# Wordclock.net
KiCad netlist of a schematic drawn in EAGLE
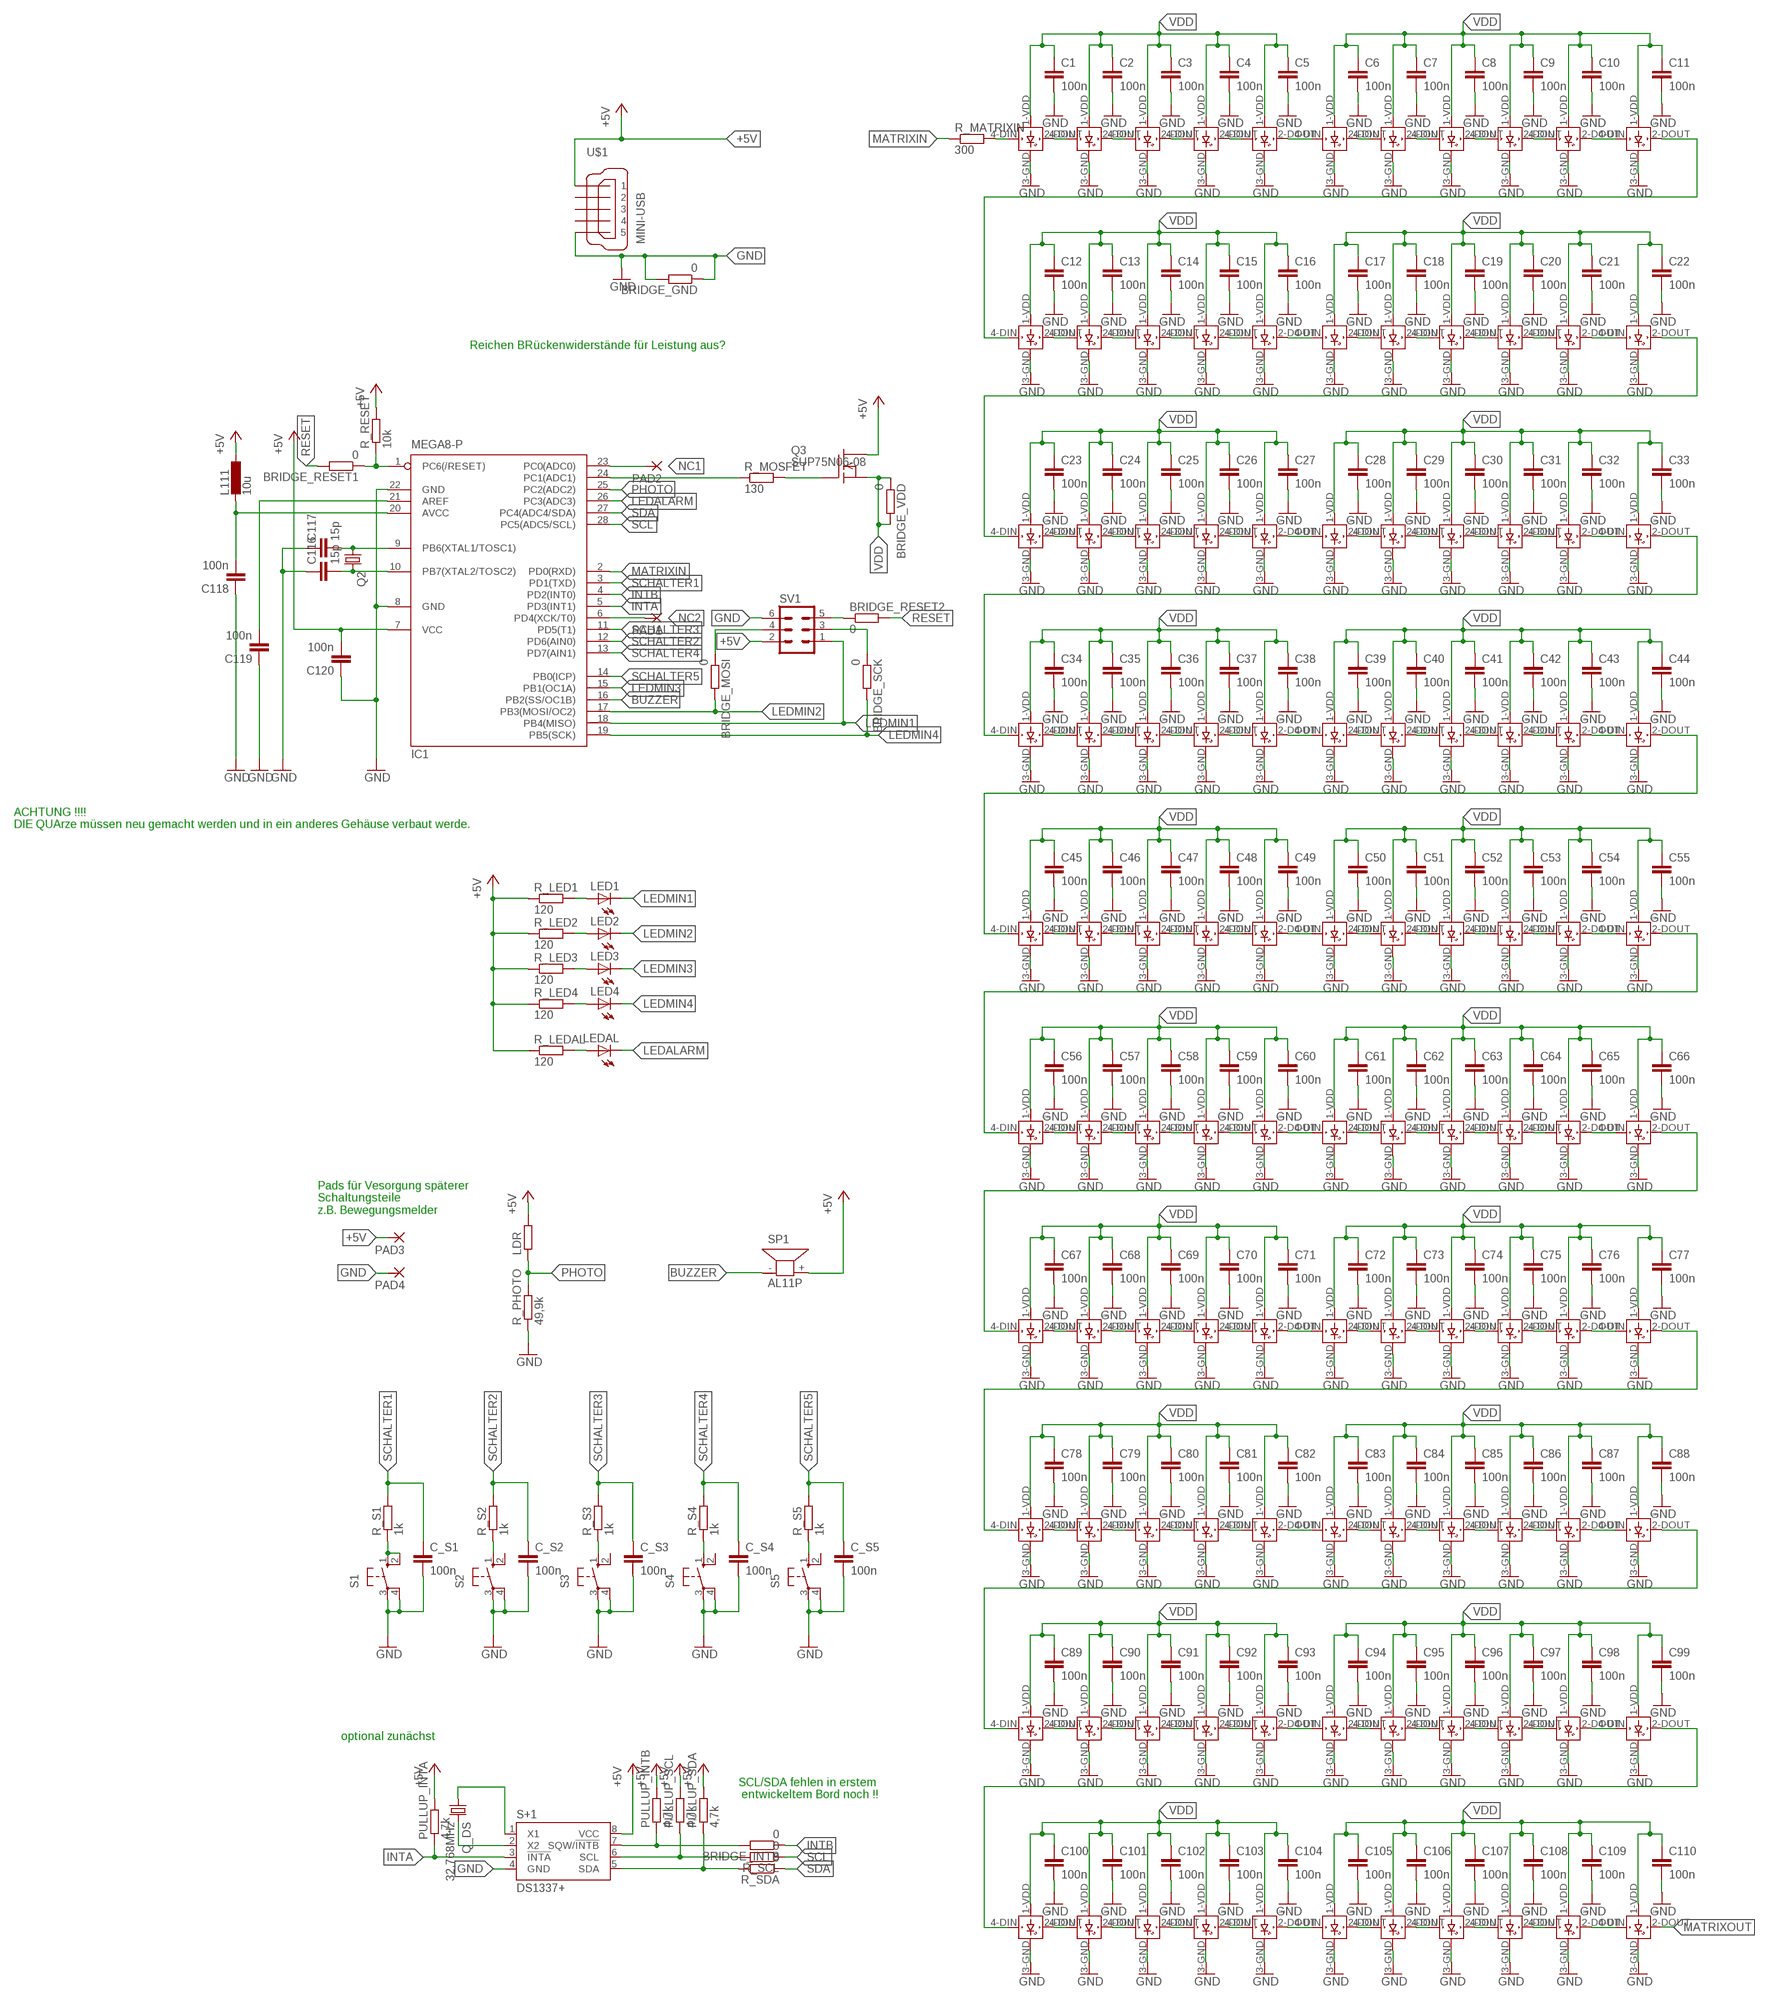
[diagram p0: schematic, sheet 1]

(export (version "E")
  (design (tool "Eeschema 10.0.6"))
  (components
    (comp (ref "BRIDGE_GND")
      (value "0")
      (footprint "eagle-import:R1206")
      (libsource (lib "eagle-import") (part "R-EU_R1206"))
    )
    (comp (ref "BRIDGE_INTB")
      (value "0")
      (footprint "eagle-import:R1206")
      (libsource (lib "eagle-import") (part "R-EU_R1206"))
    )
    (comp (ref "BRIDGE_MOSI")
      (value "0")
      (footprint "eagle-import:R1206")
      (libsource (lib "eagle-import") (part "R-EU_R1206"))
    )
    (comp (ref "BRIDGE_RESET1")
      (value "0")
      (footprint "eagle-import:M1206")
      (libsource (lib "eagle-import") (part "R-EU_M1206"))
    )
    (comp (ref "BRIDGE_RESET2")
      (value "0")
      (footprint "eagle-import:R1206")
      (libsource (lib "eagle-import") (part "R-EU_R1206"))
    )
    (comp (ref "BRIDGE_SCK")
      (value "0")
      (footprint "eagle-import:R1206")
      (libsource (lib "eagle-import") (part "R-EU_R1206"))
    )
    (comp (ref "BRIDGE_VDD")
      (value "0")
      (footprint "eagle-import:R1206")
      (libsource (lib "eagle-import") (part "R-EU_R1206"))
    )
    (comp (ref "C1")
      (value "100n")
      (footprint "eagle-import:C1310")
      (libsource (lib "eagle-import") (part "C-EUC1310"))
    )
    (comp (ref "C2")
      (value "100n")
      (footprint "eagle-import:C1310")
      (libsource (lib "eagle-import") (part "C-EUC1310"))
    )
    (comp (ref "C3")
      (value "100n")
      (footprint "eagle-import:C1310")
      (libsource (lib "eagle-import") (part "C-EUC1310"))
    )
    (comp (ref "C4")
      (value "100n")
      (footprint "eagle-import:C1310")
      (libsource (lib "eagle-import") (part "C-EUC1310"))
    )
    (comp (ref "C5")
      (value "100n")
      (footprint "eagle-import:C1310")
      (libsource (lib "eagle-import") (part "C-EUC1310"))
    )
    (comp (ref "C6")
      (value "100n")
      (footprint "eagle-import:C1310")
      (libsource (lib "eagle-import") (part "C-EUC1310"))
    )
    (comp (ref "C7")
      (value "100n")
      (footprint "eagle-import:C1310")
      (libsource (lib "eagle-import") (part "C-EUC1310"))
    )
    (comp (ref "C8")
      (value "100n")
      (footprint "eagle-import:C1310")
      (libsource (lib "eagle-import") (part "C-EUC1310"))
    )
    (comp (ref "C9")
      (value "100n")
      (footprint "eagle-import:C1310")
      (libsource (lib "eagle-import") (part "C-EUC1310"))
    )
    (comp (ref "C10")
      (value "100n")
      (footprint "eagle-import:C1310")
      (libsource (lib "eagle-import") (part "C-EUC1310"))
    )
    (comp (ref "C11")
      (value "100n")
      (footprint "eagle-import:C1310")
      (libsource (lib "eagle-import") (part "C-EUC1310"))
    )
    (comp (ref "C12")
      (value "100n")
      (footprint "eagle-import:C1310")
      (libsource (lib "eagle-import") (part "C-EUC1310"))
    )
    (comp (ref "C13")
      (value "100n")
      (footprint "eagle-import:C1310")
      (libsource (lib "eagle-import") (part "C-EUC1310"))
    )
    (comp (ref "C14")
      (value "100n")
      (footprint "eagle-import:C1310")
      (libsource (lib "eagle-import") (part "C-EUC1310"))
    )
    (comp (ref "C15")
      (value "100n")
      (footprint "eagle-import:C1310")
      (libsource (lib "eagle-import") (part "C-EUC1310"))
    )
    (comp (ref "C16")
      (value "100n")
      (footprint "eagle-import:C1310")
      (libsource (lib "eagle-import") (part "C-EUC1310"))
    )
    (comp (ref "C17")
      (value "100n")
      (footprint "eagle-import:C1310")
      (libsource (lib "eagle-import") (part "C-EUC1310"))
    )
    (comp (ref "C18")
      (value "100n")
      (footprint "eagle-import:C1310")
      (libsource (lib "eagle-import") (part "C-EUC1310"))
    )
    (comp (ref "C19")
      (value "100n")
      (footprint "eagle-import:C1310")
      (libsource (lib "eagle-import") (part "C-EUC1310"))
    )
    (comp (ref "C20")
      (value "100n")
      (footprint "eagle-import:C1310")
      (libsource (lib "eagle-import") (part "C-EUC1310"))
    )
    (comp (ref "C21")
      (value "100n")
      (footprint "eagle-import:C1310")
      (libsource (lib "eagle-import") (part "C-EUC1310"))
    )
    (comp (ref "C22")
      (value "100n")
      (footprint "eagle-import:C1310")
      (libsource (lib "eagle-import") (part "C-EUC1310"))
    )
    (comp (ref "C23")
      (value "100n")
      (footprint "eagle-import:C1310")
      (libsource (lib "eagle-import") (part "C-EUC1310"))
    )
    (comp (ref "C24")
      (value "100n")
      (footprint "eagle-import:C1310")
      (libsource (lib "eagle-import") (part "C-EUC1310"))
    )
    (comp (ref "C25")
      (value "100n")
      (footprint "eagle-import:C1310")
      (libsource (lib "eagle-import") (part "C-EUC1310"))
    )
    (comp (ref "C26")
      (value "100n")
      (footprint "eagle-import:C1310")
      (libsource (lib "eagle-import") (part "C-EUC1310"))
    )
    (comp (ref "C27")
      (value "100n")
      (footprint "eagle-import:C1310")
      (libsource (lib "eagle-import") (part "C-EUC1310"))
    )
    (comp (ref "C28")
      (value "100n")
      (footprint "eagle-import:C1310")
      (libsource (lib "eagle-import") (part "C-EUC1310"))
    )
    (comp (ref "C29")
      (value "100n")
      (footprint "eagle-import:C1310")
      (libsource (lib "eagle-import") (part "C-EUC1310"))
    )
    (comp (ref "C30")
      (value "100n")
      (footprint "eagle-import:C1310")
      (libsource (lib "eagle-import") (part "C-EUC1310"))
    )
    (comp (ref "C31")
      (value "100n")
      (footprint "eagle-import:C1310")
      (libsource (lib "eagle-import") (part "C-EUC1310"))
    )
    (comp (ref "C32")
      (value "100n")
      (footprint "eagle-import:C1310")
      (libsource (lib "eagle-import") (part "C-EUC1310"))
    )
    (comp (ref "C33")
      (value "100n")
      (footprint "eagle-import:C1310")
      (libsource (lib "eagle-import") (part "C-EUC1310"))
    )
    (comp (ref "C34")
      (value "100n")
      (footprint "eagle-import:C1310")
      (libsource (lib "eagle-import") (part "C-EUC1310"))
    )
    (comp (ref "C35")
      (value "100n")
      (footprint "eagle-import:C1310")
      (libsource (lib "eagle-import") (part "C-EUC1310"))
    )
    (comp (ref "C36")
      (value "100n")
      (footprint "eagle-import:C1310")
      (libsource (lib "eagle-import") (part "C-EUC1310"))
    )
    (comp (ref "C37")
      (value "100n")
      (footprint "eagle-import:C1310")
      (libsource (lib "eagle-import") (part "C-EUC1310"))
    )
    (comp (ref "C38")
      (value "100n")
      (footprint "eagle-import:C1310")
      (libsource (lib "eagle-import") (part "C-EUC1310"))
    )
    (comp (ref "C39")
      (value "100n")
      (footprint "eagle-import:C1310")
      (libsource (lib "eagle-import") (part "C-EUC1310"))
    )
    (comp (ref "C40")
      (value "100n")
      (footprint "eagle-import:C1310")
      (libsource (lib "eagle-import") (part "C-EUC1310"))
    )
    (comp (ref "C41")
      (value "100n")
      (footprint "eagle-import:C1310")
      (libsource (lib "eagle-import") (part "C-EUC1310"))
    )
    (comp (ref "C42")
      (value "100n")
      (footprint "eagle-import:C1310")
      (libsource (lib "eagle-import") (part "C-EUC1310"))
    )
    (comp (ref "C43")
      (value "100n")
      (footprint "eagle-import:C1310")
      (libsource (lib "eagle-import") (part "C-EUC1310"))
    )
    (comp (ref "C44")
      (value "100n")
      (footprint "eagle-import:C1310")
      (libsource (lib "eagle-import") (part "C-EUC1310"))
    )
    (comp (ref "C45")
      (value "100n")
      (footprint "eagle-import:C1310")
      (libsource (lib "eagle-import") (part "C-EUC1310"))
    )
    (comp (ref "C46")
      (value "100n")
      (footprint "eagle-import:C1310")
      (libsource (lib "eagle-import") (part "C-EUC1310"))
    )
    (comp (ref "C47")
      (value "100n")
      (footprint "eagle-import:C1310")
      (libsource (lib "eagle-import") (part "C-EUC1310"))
    )
    (comp (ref "C48")
      (value "100n")
      (footprint "eagle-import:C1310")
      (libsource (lib "eagle-import") (part "C-EUC1310"))
    )
    (comp (ref "C49")
      (value "100n")
      (footprint "eagle-import:C1310")
      (libsource (lib "eagle-import") (part "C-EUC1310"))
    )
    (comp (ref "C50")
      (value "100n")
      (footprint "eagle-import:C1310")
      (libsource (lib "eagle-import") (part "C-EUC1310"))
    )
    (comp (ref "C51")
      (value "100n")
      (footprint "eagle-import:C1310")
      (libsource (lib "eagle-import") (part "C-EUC1310"))
    )
    (comp (ref "C52")
      (value "100n")
      (footprint "eagle-import:C1310")
      (libsource (lib "eagle-import") (part "C-EUC1310"))
    )
    (comp (ref "C53")
      (value "100n")
      (footprint "eagle-import:C1310")
      (libsource (lib "eagle-import") (part "C-EUC1310"))
    )
    (comp (ref "C54")
      (value "100n")
      (footprint "eagle-import:C1310")
      (libsource (lib "eagle-import") (part "C-EUC1310"))
    )
    (comp (ref "C55")
      (value "100n")
      (footprint "eagle-import:C1310")
      (libsource (lib "eagle-import") (part "C-EUC1310"))
    )
    (comp (ref "C56")
      (value "100n")
      (footprint "eagle-import:C1310")
      (libsource (lib "eagle-import") (part "C-EUC1310"))
    )
    (comp (ref "C57")
      (value "100n")
      (footprint "eagle-import:C1310")
      (libsource (lib "eagle-import") (part "C-EUC1310"))
    )
    (comp (ref "C58")
      (value "100n")
      (footprint "eagle-import:C1310")
      (libsource (lib "eagle-import") (part "C-EUC1310"))
    )
    (comp (ref "C59")
      (value "100n")
      (footprint "eagle-import:C1310")
      (libsource (lib "eagle-import") (part "C-EUC1310"))
    )
    (comp (ref "C60")
      (value "100n")
      (footprint "eagle-import:C1310")
      (libsource (lib "eagle-import") (part "C-EUC1310"))
    )
    (comp (ref "C61")
      (value "100n")
      (footprint "eagle-import:C1310")
      (libsource (lib "eagle-import") (part "C-EUC1310"))
    )
    (comp (ref "C62")
      (value "100n")
      (footprint "eagle-import:C1310")
      (libsource (lib "eagle-import") (part "C-EUC1310"))
    )
    (comp (ref "C63")
      (value "100n")
      (footprint "eagle-import:C1310")
      (libsource (lib "eagle-import") (part "C-EUC1310"))
    )
    (comp (ref "C64")
      (value "100n")
      (footprint "eagle-import:C1310")
      (libsource (lib "eagle-import") (part "C-EUC1310"))
    )
    (comp (ref "C65")
      (value "100n")
      (footprint "eagle-import:C1310")
      (libsource (lib "eagle-import") (part "C-EUC1310"))
    )
    (comp (ref "C66")
      (value "100n")
      (footprint "eagle-import:C1310")
      (libsource (lib "eagle-import") (part "C-EUC1310"))
    )
    (comp (ref "C67")
      (value "100n")
      (footprint "eagle-import:C1310")
      (libsource (lib "eagle-import") (part "C-EUC1310"))
    )
    (comp (ref "C68")
      (value "100n")
      (footprint "eagle-import:C1310")
      (libsource (lib "eagle-import") (part "C-EUC1310"))
    )
    (comp (ref "C69")
      (value "100n")
      (footprint "eagle-import:C1310")
      (libsource (lib "eagle-import") (part "C-EUC1310"))
    )
    (comp (ref "C70")
      (value "100n")
      (footprint "eagle-import:C1310")
      (libsource (lib "eagle-import") (part "C-EUC1310"))
    )
    (comp (ref "C71")
      (value "100n")
      (footprint "eagle-import:C1310")
      (libsource (lib "eagle-import") (part "C-EUC1310"))
    )
    (comp (ref "C72")
      (value "100n")
      (footprint "eagle-import:C1310")
      (libsource (lib "eagle-import") (part "C-EUC1310"))
    )
    (comp (ref "C73")
      (value "100n")
      (footprint "eagle-import:C1310")
      (libsource (lib "eagle-import") (part "C-EUC1310"))
    )
    (comp (ref "C74")
      (value "100n")
      (footprint "eagle-import:C1310")
      (libsource (lib "eagle-import") (part "C-EUC1310"))
    )
    (comp (ref "C75")
      (value "100n")
      (footprint "eagle-import:C1310")
      (libsource (lib "eagle-import") (part "C-EUC1310"))
    )
    (comp (ref "C76")
      (value "100n")
      (footprint "eagle-import:C1310")
      (libsource (lib "eagle-import") (part "C-EUC1310"))
    )
    (comp (ref "C77")
      (value "100n")
      (footprint "eagle-import:C1310")
      (libsource (lib "eagle-import") (part "C-EUC1310"))
    )
    (comp (ref "C78")
      (value "100n")
      (footprint "eagle-import:C1310")
      (libsource (lib "eagle-import") (part "C-EUC1310"))
    )
    (comp (ref "C79")
      (value "100n")
      (footprint "eagle-import:C1310")
      (libsource (lib "eagle-import") (part "C-EUC1310"))
    )
    (comp (ref "C80")
      (value "100n")
      (footprint "eagle-import:C1310")
      (libsource (lib "eagle-import") (part "C-EUC1310"))
    )
    (comp (ref "C81")
      (value "100n")
      (footprint "eagle-import:C1310")
      (libsource (lib "eagle-import") (part "C-EUC1310"))
    )
    (comp (ref "C82")
      (value "100n")
      (footprint "eagle-import:C1310")
      (libsource (lib "eagle-import") (part "C-EUC1310"))
    )
    (comp (ref "C83")
      (value "100n")
      (footprint "eagle-import:C1310")
      (libsource (lib "eagle-import") (part "C-EUC1310"))
    )
    (comp (ref "C84")
      (value "100n")
      (footprint "eagle-import:C1310")
      (libsource (lib "eagle-import") (part "C-EUC1310"))
    )
    (comp (ref "C85")
      (value "100n")
      (footprint "eagle-import:C1310")
      (libsource (lib "eagle-import") (part "C-EUC1310"))
    )
    (comp (ref "C86")
      (value "100n")
      (footprint "eagle-import:C1310")
      (libsource (lib "eagle-import") (part "C-EUC1310"))
    )
    (comp (ref "C87")
      (value "100n")
      (footprint "eagle-import:C1310")
      (libsource (lib "eagle-import") (part "C-EUC1310"))
    )
    (comp (ref "C88")
      (value "100n")
      (footprint "eagle-import:C1310")
      (libsource (lib "eagle-import") (part "C-EUC1310"))
    )
    (comp (ref "C89")
      (value "100n")
      (footprint "eagle-import:C1310")
      (libsource (lib "eagle-import") (part "C-EUC1310"))
    )
    (comp (ref "C90")
      (value "100n")
      (footprint "eagle-import:C1310")
      (libsource (lib "eagle-import") (part "C-EUC1310"))
    )
    (comp (ref "C91")
      (value "100n")
      (footprint "eagle-import:C1310")
      (libsource (lib "eagle-import") (part "C-EUC1310"))
    )
    (comp (ref "C92")
      (value "100n")
      (footprint "eagle-import:C1310")
      (libsource (lib "eagle-import") (part "C-EUC1310"))
    )
    (comp (ref "C93")
      (value "100n")
      (footprint "eagle-import:C1310")
      (libsource (lib "eagle-import") (part "C-EUC1310"))
    )
    (comp (ref "C94")
      (value "100n")
      (footprint "eagle-import:C1310")
      (libsource (lib "eagle-import") (part "C-EUC1310"))
    )
    (comp (ref "C95")
      (value "100n")
      (footprint "eagle-import:C1310")
      (libsource (lib "eagle-import") (part "C-EUC1310"))
    )
    (comp (ref "C96")
      (value "100n")
      (footprint "eagle-import:C1310")
      (libsource (lib "eagle-import") (part "C-EUC1310"))
    )
    (comp (ref "C97")
      (value "100n")
      (footprint "eagle-import:C1310")
      (libsource (lib "eagle-import") (part "C-EUC1310"))
    )
    (comp (ref "C98")
      (value "100n")
      (footprint "eagle-import:C1310")
      (libsource (lib "eagle-import") (part "C-EUC1310"))
    )
    (comp (ref "C99")
      (value "100n")
      (footprint "eagle-import:C1310")
      (libsource (lib "eagle-import") (part "C-EUC1310"))
    )
    (comp (ref "C100")
      (value "100n")
      (footprint "eagle-import:C1310")
      (libsource (lib "eagle-import") (part "C-EUC1310"))
    )
    (comp (ref "C101")
      (value "100n")
      (footprint "eagle-import:C1310")
      (libsource (lib "eagle-import") (part "C-EUC1310"))
    )
    (comp (ref "C102")
      (value "100n")
      (footprint "eagle-import:C1310")
      (libsource (lib "eagle-import") (part "C-EUC1310"))
    )
    (comp (ref "C103")
      (value "100n")
      (footprint "eagle-import:C1310")
      (libsource (lib "eagle-import") (part "C-EUC1310"))
    )
    (comp (ref "C104")
      (value "100n")
      (footprint "eagle-import:C1310")
      (libsource (lib "eagle-import") (part "C-EUC1310"))
    )
    (comp (ref "C105")
      (value "100n")
      (footprint "eagle-import:C1310")
      (libsource (lib "eagle-import") (part "C-EUC1310"))
    )
    (comp (ref "C106")
      (value "100n")
      (footprint "eagle-import:C1310")
      (libsource (lib "eagle-import") (part "C-EUC1310"))
    )
    (comp (ref "C107")
      (value "100n")
      (footprint "eagle-import:C1310")
      (libsource (lib "eagle-import") (part "C-EUC1310"))
    )
    (comp (ref "C108")
      (value "100n")
      (footprint "eagle-import:C1310")
      (libsource (lib "eagle-import") (part "C-EUC1310"))
    )
    (comp (ref "C109")
      (value "100n")
      (footprint "eagle-import:C1310")
      (libsource (lib "eagle-import") (part "C-EUC1310"))
    )
    (comp (ref "C110")
      (value "100n")
      (footprint "eagle-import:C1310")
      (libsource (lib "eagle-import") (part "C-EUC1310"))
    )
    (comp (ref "C116")
      (value "15p")
      (footprint "eagle-import:C0805")
      (libsource (lib "eagle-import") (part "C-EUC0805"))
    )
    (comp (ref "C117")
      (value "15p")
      (footprint "eagle-import:C0805")
      (libsource (lib "eagle-import") (part "C-EUC0805"))
    )
    (comp (ref "C118")
      (value "100n")
      (footprint "eagle-import:C1206")
      (libsource (lib "eagle-import") (part "C-EUC1206"))
    )
    (comp (ref "C119")
      (value "100n")
      (footprint "eagle-import:C0805")
      (libsource (lib "eagle-import") (part "C-EUC0805"))
    )
    (comp (ref "C120")
      (value "100n")
      (footprint "eagle-import:C0805")
      (libsource (lib "eagle-import") (part "C-EUC0805"))
    )
    (comp (ref "C_S1")
      (value "100n")
      (footprint "eagle-import:C1206")
      (libsource (lib "eagle-import") (part "C-EUC1206"))
    )
    (comp (ref "C_S2")
      (value "100n")
      (footprint "eagle-import:C1206")
      (libsource (lib "eagle-import") (part "C-EUC1206"))
    )
    (comp (ref "C_S3")
      (value "100n")
      (footprint "eagle-import:C1206")
      (libsource (lib "eagle-import") (part "C-EUC1206"))
    )
    (comp (ref "C_S4")
      (value "100n")
      (footprint "eagle-import:C1206")
      (libsource (lib "eagle-import") (part "C-EUC1206"))
    )
    (comp (ref "C_S5")
      (value "100n")
      (footprint "eagle-import:C1206")
      (libsource (lib "eagle-import") (part "C-EUC1206"))
    )
    (comp (ref "IC1")
      (value "MEGA8-P")
      (footprint "eagle-import:DIL28-3")
      (libsource (lib "eagle-import") (part "MEGA8-P"))
    )
    (comp (ref "L1")
      (value "WS2812B")
      (footprint "eagle-import:WS2812B")
      (libsource (lib "eagle-import") (part "WS2812B"))
    )
    (comp (ref "L2")
      (value "WS2812B")
      (footprint "eagle-import:WS2812B")
      (libsource (lib "eagle-import") (part "WS2812B"))
    )
    (comp (ref "L3")
      (value "WS2812B")
      (footprint "eagle-import:WS2812B")
      (libsource (lib "eagle-import") (part "WS2812B"))
    )
    (comp (ref "L4")
      (value "WS2812B")
      (footprint "eagle-import:WS2812B")
      (libsource (lib "eagle-import") (part "WS2812B"))
    )
    (comp (ref "L5")
      (value "WS2812B")
      (footprint "eagle-import:WS2812B")
      (libsource (lib "eagle-import") (part "WS2812B"))
    )
    (comp (ref "L6")
      (value "WS2812B")
      (footprint "eagle-import:WS2812B")
      (libsource (lib "eagle-import") (part "WS2812B"))
    )
    (comp (ref "L7")
      (value "WS2812B")
      (footprint "eagle-import:WS2812B")
      (libsource (lib "eagle-import") (part "WS2812B"))
    )
    (comp (ref "L8")
      (value "WS2812B")
      (footprint "eagle-import:WS2812B")
      (libsource (lib "eagle-import") (part "WS2812B"))
    )
    (comp (ref "L9")
      (value "WS2812B")
      (footprint "eagle-import:WS2812B")
      (libsource (lib "eagle-import") (part "WS2812B"))
    )
    (comp (ref "L10")
      (value "WS2812B")
      (footprint "eagle-import:WS2812B")
      (libsource (lib "eagle-import") (part "WS2812B"))
    )
    (comp (ref "L11")
      (value "WS2812B")
      (footprint "eagle-import:WS2812B")
      (libsource (lib "eagle-import") (part "WS2812B"))
    )
    (comp (ref "L12")
      (value "WS2812B")
      (footprint "eagle-import:WS2812B")
      (libsource (lib "eagle-import") (part "WS2812B"))
    )
    (comp (ref "L13")
      (value "WS2812B")
      (footprint "eagle-import:WS2812B")
      (libsource (lib "eagle-import") (part "WS2812B"))
    )
    (comp (ref "L14")
      (value "WS2812B")
      (footprint "eagle-import:WS2812B")
      (libsource (lib "eagle-import") (part "WS2812B"))
    )
    (comp (ref "L15")
      (value "WS2812B")
      (footprint "eagle-import:WS2812B")
      (libsource (lib "eagle-import") (part "WS2812B"))
    )
    (comp (ref "L16")
      (value "WS2812B")
      (footprint "eagle-import:WS2812B")
      (libsource (lib "eagle-import") (part "WS2812B"))
    )
    (comp (ref "L17")
      (value "WS2812B")
      (footprint "eagle-import:WS2812B")
      (libsource (lib "eagle-import") (part "WS2812B"))
    )
    (comp (ref "L18")
      (value "WS2812B")
      (footprint "eagle-import:WS2812B")
      (libsource (lib "eagle-import") (part "WS2812B"))
    )
    (comp (ref "L19")
      (value "WS2812B")
      (footprint "eagle-import:WS2812B")
      (libsource (lib "eagle-import") (part "WS2812B"))
    )
    (comp (ref "L20")
      (value "WS2812B")
      (footprint "eagle-import:WS2812B")
      (libsource (lib "eagle-import") (part "WS2812B"))
    )
    (comp (ref "L21")
      (value "WS2812B")
      (footprint "eagle-import:WS2812B")
      (libsource (lib "eagle-import") (part "WS2812B"))
    )
    (comp (ref "L22")
      (value "WS2812B")
      (footprint "eagle-import:WS2812B")
      (libsource (lib "eagle-import") (part "WS2812B"))
    )
    (comp (ref "L23")
      (value "WS2812B")
      (footprint "eagle-import:WS2812B")
      (libsource (lib "eagle-import") (part "WS2812B"))
    )
    (comp (ref "L24")
      (value "WS2812B")
      (footprint "eagle-import:WS2812B")
      (libsource (lib "eagle-import") (part "WS2812B"))
    )
    (comp (ref "L25")
      (value "WS2812B")
      (footprint "eagle-import:WS2812B")
      (libsource (lib "eagle-import") (part "WS2812B"))
    )
    (comp (ref "L26")
      (value "WS2812B")
      (footprint "eagle-import:WS2812B")
      (libsource (lib "eagle-import") (part "WS2812B"))
    )
    (comp (ref "L27")
      (value "WS2812B")
      (footprint "eagle-import:WS2812B")
      (libsource (lib "eagle-import") (part "WS2812B"))
    )
    (comp (ref "L28")
      (value "WS2812B")
      (footprint "eagle-import:WS2812B")
      (libsource (lib "eagle-import") (part "WS2812B"))
    )
    (comp (ref "L29")
      (value "WS2812B")
      (footprint "eagle-import:WS2812B")
      (libsource (lib "eagle-import") (part "WS2812B"))
    )
    (comp (ref "L30")
      (value "WS2812B")
      (footprint "eagle-import:WS2812B")
      (libsource (lib "eagle-import") (part "WS2812B"))
    )
    (comp (ref "L31")
      (value "WS2812B")
      (footprint "eagle-import:WS2812B")
      (libsource (lib "eagle-import") (part "WS2812B"))
    )
    (comp (ref "L32")
      (value "WS2812B")
      (footprint "eagle-import:WS2812B")
      (libsource (lib "eagle-import") (part "WS2812B"))
    )
    (comp (ref "L33")
      (value "WS2812B")
      (footprint "eagle-import:WS2812B")
      (libsource (lib "eagle-import") (part "WS2812B"))
    )
    (comp (ref "L34")
      (value "WS2812B")
      (footprint "eagle-import:WS2812B")
      (libsource (lib "eagle-import") (part "WS2812B"))
    )
    (comp (ref "L35")
      (value "WS2812B")
      (footprint "eagle-import:WS2812B")
      (libsource (lib "eagle-import") (part "WS2812B"))
    )
    (comp (ref "L36")
      (value "WS2812B")
      (footprint "eagle-import:WS2812B")
      (libsource (lib "eagle-import") (part "WS2812B"))
    )
    (comp (ref "L37")
      (value "WS2812B")
      (footprint "eagle-import:WS2812B")
      (libsource (lib "eagle-import") (part "WS2812B"))
    )
    (comp (ref "L38")
      (value "WS2812B")
      (footprint "eagle-import:WS2812B")
      (libsource (lib "eagle-import") (part "WS2812B"))
    )
    (comp (ref "L39")
      (value "WS2812B")
      (footprint "eagle-import:WS2812B")
      (libsource (lib "eagle-import") (part "WS2812B"))
    )
    (comp (ref "L40")
      (value "WS2812B")
      (footprint "eagle-import:WS2812B")
      (libsource (lib "eagle-import") (part "WS2812B"))
    )
    (comp (ref "L41")
      (value "WS2812B")
      (footprint "eagle-import:WS2812B")
      (libsource (lib "eagle-import") (part "WS2812B"))
    )
    (comp (ref "L42")
      (value "WS2812B")
      (footprint "eagle-import:WS2812B")
      (libsource (lib "eagle-import") (part "WS2812B"))
    )
    (comp (ref "L43")
      (value "WS2812B")
      (footprint "eagle-import:WS2812B")
      (libsource (lib "eagle-import") (part "WS2812B"))
    )
    (comp (ref "L44")
      (value "WS2812B")
      (footprint "eagle-import:WS2812B")
      (libsource (lib "eagle-import") (part "WS2812B"))
    )
    (comp (ref "L45")
      (value "WS2812B")
      (footprint "eagle-import:WS2812B")
      (libsource (lib "eagle-import") (part "WS2812B"))
    )
    (comp (ref "L46")
      (value "WS2812B")
      (footprint "eagle-import:WS2812B")
      (libsource (lib "eagle-import") (part "WS2812B"))
    )
    (comp (ref "L47")
      (value "WS2812B")
      (footprint "eagle-import:WS2812B")
      (libsource (lib "eagle-import") (part "WS2812B"))
    )
    (comp (ref "L48")
      (value "WS2812B")
      (footprint "eagle-import:WS2812B")
      (libsource (lib "eagle-import") (part "WS2812B"))
    )
    (comp (ref "L49")
      (value "WS2812B")
      (footprint "eagle-import:WS2812B")
      (libsource (lib "eagle-import") (part "WS2812B"))
    )
    (comp (ref "L50")
      (value "WS2812B")
      (footprint "eagle-import:WS2812B")
      (libsource (lib "eagle-import") (part "WS2812B"))
    )
    (comp (ref "L51")
      (value "WS2812B")
      (footprint "eagle-import:WS2812B")
      (libsource (lib "eagle-import") (part "WS2812B"))
    )
    (comp (ref "L52")
      (value "WS2812B")
      (footprint "eagle-import:WS2812B")
      (libsource (lib "eagle-import") (part "WS2812B"))
    )
    (comp (ref "L53")
      (value "WS2812B")
      (footprint "eagle-import:WS2812B")
      (libsource (lib "eagle-import") (part "WS2812B"))
    )
    (comp (ref "L54")
      (value "WS2812B")
      (footprint "eagle-import:WS2812B")
      (libsource (lib "eagle-import") (part "WS2812B"))
    )
    (comp (ref "L55")
      (value "WS2812B")
      (footprint "eagle-import:WS2812B")
      (libsource (lib "eagle-import") (part "WS2812B"))
    )
    (comp (ref "L56")
      (value "WS2812B")
      (footprint "eagle-import:WS2812B")
      (libsource (lib "eagle-import") (part "WS2812B"))
    )
    (comp (ref "L57")
      (value "WS2812B")
      (footprint "eagle-import:WS2812B")
      (libsource (lib "eagle-import") (part "WS2812B"))
    )
    (comp (ref "L58")
      (value "WS2812B")
      (footprint "eagle-import:WS2812B")
      (libsource (lib "eagle-import") (part "WS2812B"))
    )
    (comp (ref "L59")
      (value "WS2812B")
      (footprint "eagle-import:WS2812B")
      (libsource (lib "eagle-import") (part "WS2812B"))
    )
    (comp (ref "L60")
      (value "WS2812B")
      (footprint "eagle-import:WS2812B")
      (libsource (lib "eagle-import") (part "WS2812B"))
    )
    (comp (ref "L61")
      (value "WS2812B")
      (footprint "eagle-import:WS2812B")
      (libsource (lib "eagle-import") (part "WS2812B"))
    )
    (comp (ref "L62")
      (value "WS2812B")
      (footprint "eagle-import:WS2812B")
      (libsource (lib "eagle-import") (part "WS2812B"))
    )
    (comp (ref "L63")
      (value "WS2812B")
      (footprint "eagle-import:WS2812B")
      (libsource (lib "eagle-import") (part "WS2812B"))
    )
    (comp (ref "L64")
      (value "WS2812B")
      (footprint "eagle-import:WS2812B")
      (libsource (lib "eagle-import") (part "WS2812B"))
    )
    (comp (ref "L65")
      (value "WS2812B")
      (footprint "eagle-import:WS2812B")
      (libsource (lib "eagle-import") (part "WS2812B"))
    )
    (comp (ref "L66")
      (value "WS2812B")
      (footprint "eagle-import:WS2812B")
      (libsource (lib "eagle-import") (part "WS2812B"))
    )
    (comp (ref "L67")
      (value "WS2812B")
      (footprint "eagle-import:WS2812B")
      (libsource (lib "eagle-import") (part "WS2812B"))
    )
    (comp (ref "L68")
      (value "WS2812B")
      (footprint "eagle-import:WS2812B")
      (libsource (lib "eagle-import") (part "WS2812B"))
    )
    (comp (ref "L69")
      (value "WS2812B")
      (footprint "eagle-import:WS2812B")
      (libsource (lib "eagle-import") (part "WS2812B"))
    )
    (comp (ref "L70")
      (value "WS2812B")
      (footprint "eagle-import:WS2812B")
      (libsource (lib "eagle-import") (part "WS2812B"))
    )
    (comp (ref "L71")
      (value "WS2812B")
      (footprint "eagle-import:WS2812B")
      (libsource (lib "eagle-import") (part "WS2812B"))
    )
    (comp (ref "L72")
      (value "WS2812B")
      (footprint "eagle-import:WS2812B")
      (libsource (lib "eagle-import") (part "WS2812B"))
    )
    (comp (ref "L73")
      (value "WS2812B")
      (footprint "eagle-import:WS2812B")
      (libsource (lib "eagle-import") (part "WS2812B"))
    )
    (comp (ref "L74")
      (value "WS2812B")
      (footprint "eagle-import:WS2812B")
      (libsource (lib "eagle-import") (part "WS2812B"))
    )
    (comp (ref "L75")
      (value "WS2812B")
      (footprint "eagle-import:WS2812B")
      (libsource (lib "eagle-import") (part "WS2812B"))
    )
    (comp (ref "L76")
      (value "WS2812B")
      (footprint "eagle-import:WS2812B")
      (libsource (lib "eagle-import") (part "WS2812B"))
    )
    (comp (ref "L77")
      (value "WS2812B")
      (footprint "eagle-import:WS2812B")
      (libsource (lib "eagle-import") (part "WS2812B"))
    )
    (comp (ref "L78")
      (value "WS2812B")
      (footprint "eagle-import:WS2812B")
      (libsource (lib "eagle-import") (part "WS2812B"))
    )
    (comp (ref "L79")
      (value "WS2812B")
      (footprint "eagle-import:WS2812B")
      (libsource (lib "eagle-import") (part "WS2812B"))
    )
    (comp (ref "L80")
      (value "WS2812B")
      (footprint "eagle-import:WS2812B")
      (libsource (lib "eagle-import") (part "WS2812B"))
    )
    (comp (ref "L81")
      (value "WS2812B")
      (footprint "eagle-import:WS2812B")
      (libsource (lib "eagle-import") (part "WS2812B"))
    )
    (comp (ref "L82")
      (value "WS2812B")
      (footprint "eagle-import:WS2812B")
      (libsource (lib "eagle-import") (part "WS2812B"))
    )
    (comp (ref "L83")
      (value "WS2812B")
      (footprint "eagle-import:WS2812B")
      (libsource (lib "eagle-import") (part "WS2812B"))
    )
    (comp (ref "L84")
      (value "WS2812B")
      (footprint "eagle-import:WS2812B")
      (libsource (lib "eagle-import") (part "WS2812B"))
    )
    (comp (ref "L85")
      (value "WS2812B")
      (footprint "eagle-import:WS2812B")
      (libsource (lib "eagle-import") (part "WS2812B"))
    )
    (comp (ref "L86")
      (value "WS2812B")
      (footprint "eagle-import:WS2812B")
      (libsource (lib "eagle-import") (part "WS2812B"))
    )
    (comp (ref "L87")
      (value "WS2812B")
      (footprint "eagle-import:WS2812B")
      (libsource (lib "eagle-import") (part "WS2812B"))
    )
    (comp (ref "L88")
      (value "WS2812B")
      (footprint "eagle-import:WS2812B")
      (libsource (lib "eagle-import") (part "WS2812B"))
    )
    (comp (ref "L89")
      (value "WS2812B")
      (footprint "eagle-import:WS2812B")
      (libsource (lib "eagle-import") (part "WS2812B"))
    )
    (comp (ref "L90")
      (value "WS2812B")
      (footprint "eagle-import:WS2812B")
      (libsource (lib "eagle-import") (part "WS2812B"))
    )
    (comp (ref "L91")
      (value "WS2812B")
      (footprint "eagle-import:WS2812B")
      (libsource (lib "eagle-import") (part "WS2812B"))
    )
    (comp (ref "L92")
      (value "WS2812B")
      (footprint "eagle-import:WS2812B")
      (libsource (lib "eagle-import") (part "WS2812B"))
    )
    (comp (ref "L93")
      (value "WS2812B")
      (footprint "eagle-import:WS2812B")
      (libsource (lib "eagle-import") (part "WS2812B"))
    )
    (comp (ref "L94")
      (value "WS2812B")
      (footprint "eagle-import:WS2812B")
      (libsource (lib "eagle-import") (part "WS2812B"))
    )
    (comp (ref "L95")
      (value "WS2812B")
      (footprint "eagle-import:WS2812B")
      (libsource (lib "eagle-import") (part "WS2812B"))
    )
    (comp (ref "L96")
      (value "WS2812B")
      (footprint "eagle-import:WS2812B")
      (libsource (lib "eagle-import") (part "WS2812B"))
    )
    (comp (ref "L97")
      (value "WS2812B")
      (footprint "eagle-import:WS2812B")
      (libsource (lib "eagle-import") (part "WS2812B"))
    )
    (comp (ref "L98")
      (value "WS2812B")
      (footprint "eagle-import:WS2812B")
      (libsource (lib "eagle-import") (part "WS2812B"))
    )
    (comp (ref "L99")
      (value "WS2812B")
      (footprint "eagle-import:WS2812B")
      (libsource (lib "eagle-import") (part "WS2812B"))
    )
    (comp (ref "L100")
      (value "WS2812B")
      (footprint "eagle-import:WS2812B")
      (libsource (lib "eagle-import") (part "WS2812B"))
    )
    (comp (ref "L101")
      (value "WS2812B")
      (footprint "eagle-import:WS2812B")
      (libsource (lib "eagle-import") (part "WS2812B"))
    )
    (comp (ref "L102")
      (value "WS2812B")
      (footprint "eagle-import:WS2812B")
      (libsource (lib "eagle-import") (part "WS2812B"))
    )
    (comp (ref "L103")
      (value "WS2812B")
      (footprint "eagle-import:WS2812B")
      (libsource (lib "eagle-import") (part "WS2812B"))
    )
    (comp (ref "L104")
      (value "WS2812B")
      (footprint "eagle-import:WS2812B")
      (libsource (lib "eagle-import") (part "WS2812B"))
    )
    (comp (ref "L105")
      (value "WS2812B")
      (footprint "eagle-import:WS2812B")
      (libsource (lib "eagle-import") (part "WS2812B"))
    )
    (comp (ref "L106")
      (value "WS2812B")
      (footprint "eagle-import:WS2812B")
      (libsource (lib "eagle-import") (part "WS2812B"))
    )
    (comp (ref "L107")
      (value "WS2812B")
      (footprint "eagle-import:WS2812B")
      (libsource (lib "eagle-import") (part "WS2812B"))
    )
    (comp (ref "L108")
      (value "WS2812B")
      (footprint "eagle-import:WS2812B")
      (libsource (lib "eagle-import") (part "WS2812B"))
    )
    (comp (ref "L109")
      (value "WS2812B")
      (footprint "eagle-import:WS2812B")
      (libsource (lib "eagle-import") (part "WS2812B"))
    )
    (comp (ref "L110")
      (value "WS2812B")
      (footprint "eagle-import:WS2812B")
      (libsource (lib "eagle-import") (part "WS2812B"))
    )
    (comp (ref "L111")
      (value "10u")
      (footprint "eagle-import:L2012C")
      (libsource (lib "eagle-import") (part "L-EUL2012C"))
    )
    (comp (ref "LDR")
      (value "R-EU_0204/5")
      (footprint "eagle-import:0204_5")
      (libsource (lib "eagle-import") (part "R-EU_0204/5"))
    )
    (comp (ref "LED1")
      (value "LEDCHIPLED_1206")
      (footprint "eagle-import:CHIPLED_1206")
      (libsource (lib "eagle-import") (part "LEDCHIPLED_1206"))
    )
    (comp (ref "LED2")
      (value "LEDCHIPLED_1206")
      (footprint "eagle-import:CHIPLED_1206")
      (libsource (lib "eagle-import") (part "LEDCHIPLED_1206"))
    )
    (comp (ref "LED3")
      (value "LEDCHIPLED_1206")
      (footprint "eagle-import:CHIPLED_1206")
      (libsource (lib "eagle-import") (part "LEDCHIPLED_1206"))
    )
    (comp (ref "LED4")
      (value "LEDCHIPLED_1206")
      (footprint "eagle-import:CHIPLED_1206")
      (libsource (lib "eagle-import") (part "LEDCHIPLED_1206"))
    )
    (comp (ref "LEDAL")
      (value "LEDCHIPLED_1206")
      (footprint "eagle-import:CHIPLED_1206")
      (libsource (lib "eagle-import") (part "LEDCHIPLED_1206"))
    )
    (comp (ref "PAD1")
      (value "2,54/1,1")
      (footprint "eagle-import:2,54_1,1")
      (libsource (lib "eagle-import") (part "2,54/1,1"))
    )
    (comp (ref "PAD2")
      (value "2,54/1,1")
      (footprint "eagle-import:2,54_1,1")
      (libsource (lib "eagle-import") (part "2,54/1,1"))
    )
    (comp (ref "PAD3")
      (value "2,54/1,1")
      (footprint "eagle-import:2,54_1,1")
      (libsource (lib "eagle-import") (part "2,54/1,1"))
    )
    (comp (ref "PAD4")
      (value "2,54/1,1")
      (footprint "eagle-import:2,54_1,1")
      (libsource (lib "eagle-import") (part "2,54/1,1"))
    )
    (comp (ref "PULLUP_INTA")
      (value "4,7k")
      (footprint "eagle-import:R1206")
      (libsource (lib "eagle-import") (part "R-EU_R1206"))
    )
    (comp (ref "PULLUP_INTB")
      (value "4,7k")
      (footprint "eagle-import:R1206")
      (libsource (lib "eagle-import") (part "R-EU_R1206"))
    )
    (comp (ref "PULLUP_SCL")
      (value "4,7k")
      (footprint "eagle-import:R1206")
      (libsource (lib "eagle-import") (part "R-EU_R1206"))
    )
    (comp (ref "PULLUP_SDA")
      (value "4,7k")
      (footprint "eagle-import:R1206")
      (libsource (lib "eagle-import") (part "R-EU_R1206"))
    )
    (comp (ref "Q2")
      (value "CRYSTALHC49S")
      (footprint "eagle-import:HC49_S")
      (libsource (lib "eagle-import") (part "CRYSTALHC49S"))
    )
    (comp (ref "Q3")
      (value "SUP75N06-08")
      (footprint "eagle-import:TO220")
      (libsource (lib "eagle-import") (part "SUP75N06-08"))
    )
    (comp (ref "Q_DS")
      (value "32,768MHz")
      (footprint "eagle-import:HC49_S")
      (libsource (lib "eagle-import") (part "CRYSTALHC49S"))
    )
    (comp (ref "R_LED1")
      (value "120")
      (footprint "eagle-import:M1206")
      (libsource (lib "eagle-import") (part "R-EU_M1206"))
    )
    (comp (ref "R_LED2")
      (value "120")
      (footprint "eagle-import:M1206")
      (libsource (lib "eagle-import") (part "R-EU_M1206"))
    )
    (comp (ref "R_LED3")
      (value "120")
      (footprint "eagle-import:M1206")
      (libsource (lib "eagle-import") (part "R-EU_M1206"))
    )
    (comp (ref "R_LED4")
      (value "120")
      (footprint "eagle-import:M1206")
      (libsource (lib "eagle-import") (part "R-EU_M1206"))
    )
    (comp (ref "R_LEDAL")
      (value "120")
      (footprint "eagle-import:M1206")
      (libsource (lib "eagle-import") (part "R-EU_M1206"))
    )
    (comp (ref "R_MATRIXIN")
      (value "300")
      (footprint "eagle-import:R1206")
      (libsource (lib "eagle-import") (part "R-EU_R1206"))
    )
    (comp (ref "R_MOSFET")
      (value "130")
      (footprint "eagle-import:R1206")
      (libsource (lib "eagle-import") (part "R-EU_R1206"))
    )
    (comp (ref "R_PHOTO")
      (value "49,9k")
      (footprint "eagle-import:M1206")
      (libsource (lib "eagle-import") (part "R-EU_M1206"))
    )
    (comp (ref "R_RESET")
      (value "10k")
      (footprint "eagle-import:M1206")
      (libsource (lib "eagle-import") (part "R-EU_M1206"))
    )
    (comp (ref "R_S1")
      (value "1k")
      (footprint "eagle-import:M1206")
      (libsource (lib "eagle-import") (part "R-EU_M1206"))
    )
    (comp (ref "R_S2")
      (value "1k")
      (footprint "eagle-import:M1206")
      (libsource (lib "eagle-import") (part "R-EU_M1206"))
    )
    (comp (ref "R_S3")
      (value "1k")
      (footprint "eagle-import:M1206")
      (libsource (lib "eagle-import") (part "R-EU_M1206"))
    )
    (comp (ref "R_S4")
      (value "1k")
      (footprint "eagle-import:M1206")
      (libsource (lib "eagle-import") (part "R-EU_M1206"))
    )
    (comp (ref "R_S5")
      (value "1k")
      (footprint "eagle-import:M1206")
      (libsource (lib "eagle-import") (part "R-EU_M1206"))
    )
    (comp (ref "R_SCL")
      (value "0")
      (footprint "eagle-import:R1206")
      (libsource (lib "eagle-import") (part "R-EU_R1206"))
    )
    (comp (ref "R_SDA")
      (value "0")
      (footprint "eagle-import:R1206")
      (libsource (lib "eagle-import") (part "R-EU_R1206"))
    )
    (comp (ref "S+1")
      (value "DS1337+")
      (footprint "eagle-import:DIL8")
      (libsource (lib "eagle-import") (part "DS1337+"))
    )
    (comp (ref "S1")
      (value "10-XX")
      (footprint "eagle-import:B3F-10XX")
      (fields (field (name "MPN") "B3F-1000"))
      (libsource (lib "eagle-import") (part "10-XX"))
    )
    (comp (ref "S2")
      (value "10-XX")
      (footprint "eagle-import:B3F-10XX")
      (fields (field (name "MPN") "B3F-1000"))
      (libsource (lib "eagle-import") (part "10-XX"))
    )
    (comp (ref "S3")
      (value "10-XX")
      (footprint "eagle-import:B3F-10XX")
      (fields (field (name "MPN") "B3F-1000"))
      (libsource (lib "eagle-import") (part "10-XX"))
    )
    (comp (ref "S4")
      (value "10-XX")
      (footprint "eagle-import:B3F-10XX")
      (fields (field (name "MPN") "B3F-1000"))
      (libsource (lib "eagle-import") (part "10-XX"))
    )
    (comp (ref "S5")
      (value "10-XX")
      (footprint "eagle-import:B3F-10XX")
      (fields (field (name "MPN") "B3F-1000"))
      (libsource (lib "eagle-import") (part "10-XX"))
    )
    (comp (ref "SP1")
      (value "AL11P")
      (footprint "eagle-import:AL11P")
      (libsource (lib "eagle-import") (part "AL11P"))
    )
    (comp (ref "SV1")
      (value "ML6L")
      (footprint "eagle-import:ML6L")
      (libsource (lib "eagle-import") (part "ML6L"))
    )
    (comp (ref "U$1")
      (value "MINI-USB")
      (footprint "eagle-import:MINI-USB")
      (libsource (lib "eagle-import") (part "MINI-USB"))
    )
  )
  (nets
    (net (code "1") (name "+5V") (class "Default")
      (node (ref "C120") (pin "2") (pinfunction "2_2") (pintype "passive"))
      (node (ref "IC1") (pin "7") (pinfunction "VCC_7") (pintype "power_in"))
      (node (ref "L111") (pin "1") (pinfunction "1_1") (pintype "passive"))
      (node (ref "LDR") (pin "2") (pinfunction "2_2") (pintype "passive"))
      (node (ref "PAD3") (pin "1") (pinfunction "P_1") (pintype "passive"))
      (node (ref "PULLUP_INTA") (pin "2") (pinfunction "2_2") (pintype "passive"))
      (node (ref "PULLUP_INTB") (pin "2") (pinfunction "2_2") (pintype "passive"))
      (node (ref "PULLUP_SCL") (pin "2") (pinfunction "2_2") (pintype "passive"))
      (node (ref "PULLUP_SDA") (pin "2") (pinfunction "2_2") (pintype "passive"))
      (node (ref "Q3") (pin "2") (pinfunction "D_2") (pintype "passive"))
      (node (ref "R_LED1") (pin "1") (pinfunction "1_1") (pintype "passive"))
      (node (ref "R_LED2") (pin "1") (pinfunction "1_1") (pintype "passive"))
      (node (ref "R_LED3") (pin "1") (pinfunction "1_1") (pintype "passive"))
      (node (ref "R_LED4") (pin "1") (pinfunction "1_1") (pintype "passive"))
      (node (ref "R_LEDAL") (pin "1") (pinfunction "1_1") (pintype "passive"))
      (node (ref "R_RESET") (pin "2") (pinfunction "2_2") (pintype "passive"))
      (node (ref "S+1") (pin "8") (pinfunction "VCC_8") (pintype "bidirectional"))
      (node (ref "SP1") (pin "+") (pinfunction "2_+") (pintype "passive"))
      (node (ref "SV1") (pin "2") (pinfunction "2_2") (pintype "passive"))
      (node (ref "U$1") (pin "1") (pinfunction "1_1") (pintype "input"))
    )
    (net (code "2") (name "BUZZER") (class "Default")
      (node (ref "IC1") (pin "16") (pinfunction "PB2(SS/OC1B)_16") (pintype "bidirectional"))
      (node (ref "SP1") (pin "-") (pinfunction "1_-") (pintype "passive"))
    )
    (net (code "3") (name "GND") (class "Default")
      (node (ref "BRIDGE_GND") (pin "1") (pinfunction "1_1") (pintype "passive"))
      (node (ref "BRIDGE_GND") (pin "2") (pinfunction "2_2") (pintype "passive"))
      (node (ref "C1") (pin "2") (pinfunction "2_2") (pintype "passive"))
      (node (ref "C10") (pin "2") (pinfunction "2_2") (pintype "passive"))
      (node (ref "C100") (pin "2") (pinfunction "2_2") (pintype "passive"))
      (node (ref "C101") (pin "2") (pinfunction "2_2") (pintype "passive"))
      (node (ref "C102") (pin "2") (pinfunction "2_2") (pintype "passive"))
      (node (ref "C103") (pin "2") (pinfunction "2_2") (pintype "passive"))
      (node (ref "C104") (pin "2") (pinfunction "2_2") (pintype "passive"))
      (node (ref "C105") (pin "2") (pinfunction "2_2") (pintype "passive"))
      (node (ref "C106") (pin "2") (pinfunction "2_2") (pintype "passive"))
      (node (ref "C107") (pin "2") (pinfunction "2_2") (pintype "passive"))
      (node (ref "C108") (pin "2") (pinfunction "2_2") (pintype "passive"))
      (node (ref "C109") (pin "2") (pinfunction "2_2") (pintype "passive"))
      (node (ref "C11") (pin "2") (pinfunction "2_2") (pintype "passive"))
      (node (ref "C110") (pin "2") (pinfunction "2_2") (pintype "passive"))
      (node (ref "C116") (pin "1") (pinfunction "1_1") (pintype "passive"))
      (node (ref "C117") (pin "1") (pinfunction "1_1") (pintype "passive"))
      (node (ref "C118") (pin "1") (pinfunction "1_1") (pintype "passive"))
      (node (ref "C119") (pin "1") (pinfunction "1_1") (pintype "passive"))
      (node (ref "C12") (pin "2") (pinfunction "2_2") (pintype "passive"))
      (node (ref "C120") (pin "1") (pinfunction "1_1") (pintype "passive"))
      (node (ref "C13") (pin "2") (pinfunction "2_2") (pintype "passive"))
      (node (ref "C14") (pin "2") (pinfunction "2_2") (pintype "passive"))
      (node (ref "C15") (pin "2") (pinfunction "2_2") (pintype "passive"))
      (node (ref "C16") (pin "2") (pinfunction "2_2") (pintype "passive"))
      (node (ref "C17") (pin "2") (pinfunction "2_2") (pintype "passive"))
      (node (ref "C18") (pin "2") (pinfunction "2_2") (pintype "passive"))
      (node (ref "C19") (pin "2") (pinfunction "2_2") (pintype "passive"))
      (node (ref "C2") (pin "2") (pinfunction "2_2") (pintype "passive"))
      (node (ref "C20") (pin "2") (pinfunction "2_2") (pintype "passive"))
      (node (ref "C21") (pin "2") (pinfunction "2_2") (pintype "passive"))
      (node (ref "C22") (pin "2") (pinfunction "2_2") (pintype "passive"))
      (node (ref "C23") (pin "2") (pinfunction "2_2") (pintype "passive"))
      (node (ref "C24") (pin "2") (pinfunction "2_2") (pintype "passive"))
      (node (ref "C25") (pin "2") (pinfunction "2_2") (pintype "passive"))
      (node (ref "C26") (pin "2") (pinfunction "2_2") (pintype "passive"))
      (node (ref "C27") (pin "2") (pinfunction "2_2") (pintype "passive"))
      (node (ref "C28") (pin "2") (pinfunction "2_2") (pintype "passive"))
      (node (ref "C29") (pin "2") (pinfunction "2_2") (pintype "passive"))
      (node (ref "C3") (pin "2") (pinfunction "2_2") (pintype "passive"))
      (node (ref "C30") (pin "2") (pinfunction "2_2") (pintype "passive"))
      (node (ref "C31") (pin "2") (pinfunction "2_2") (pintype "passive"))
      (node (ref "C32") (pin "2") (pinfunction "2_2") (pintype "passive"))
      (node (ref "C33") (pin "2") (pinfunction "2_2") (pintype "passive"))
      (node (ref "C34") (pin "2") (pinfunction "2_2") (pintype "passive"))
      (node (ref "C35") (pin "2") (pinfunction "2_2") (pintype "passive"))
      (node (ref "C36") (pin "2") (pinfunction "2_2") (pintype "passive"))
      (node (ref "C37") (pin "2") (pinfunction "2_2") (pintype "passive"))
      (node (ref "C38") (pin "2") (pinfunction "2_2") (pintype "passive"))
      (node (ref "C39") (pin "2") (pinfunction "2_2") (pintype "passive"))
      (node (ref "C4") (pin "2") (pinfunction "2_2") (pintype "passive"))
      (node (ref "C40") (pin "2") (pinfunction "2_2") (pintype "passive"))
      (node (ref "C41") (pin "2") (pinfunction "2_2") (pintype "passive"))
      (node (ref "C42") (pin "2") (pinfunction "2_2") (pintype "passive"))
      (node (ref "C43") (pin "2") (pinfunction "2_2") (pintype "passive"))
      (node (ref "C44") (pin "2") (pinfunction "2_2") (pintype "passive"))
      (node (ref "C45") (pin "2") (pinfunction "2_2") (pintype "passive"))
      (node (ref "C46") (pin "2") (pinfunction "2_2") (pintype "passive"))
      (node (ref "C47") (pin "2") (pinfunction "2_2") (pintype "passive"))
      (node (ref "C48") (pin "2") (pinfunction "2_2") (pintype "passive"))
      (node (ref "C49") (pin "2") (pinfunction "2_2") (pintype "passive"))
      (node (ref "C5") (pin "2") (pinfunction "2_2") (pintype "passive"))
      (node (ref "C50") (pin "2") (pinfunction "2_2") (pintype "passive"))
      (node (ref "C51") (pin "2") (pinfunction "2_2") (pintype "passive"))
      (node (ref "C52") (pin "2") (pinfunction "2_2") (pintype "passive"))
      (node (ref "C53") (pin "2") (pinfunction "2_2") (pintype "passive"))
      (node (ref "C54") (pin "2") (pinfunction "2_2") (pintype "passive"))
      (node (ref "C55") (pin "2") (pinfunction "2_2") (pintype "passive"))
      (node (ref "C56") (pin "2") (pinfunction "2_2") (pintype "passive"))
      (node (ref "C57") (pin "2") (pinfunction "2_2") (pintype "passive"))
      (node (ref "C58") (pin "2") (pinfunction "2_2") (pintype "passive"))
      (node (ref "C59") (pin "2") (pinfunction "2_2") (pintype "passive"))
      (node (ref "C6") (pin "2") (pinfunction "2_2") (pintype "passive"))
      (node (ref "C60") (pin "2") (pinfunction "2_2") (pintype "passive"))
      (node (ref "C61") (pin "2") (pinfunction "2_2") (pintype "passive"))
      (node (ref "C62") (pin "2") (pinfunction "2_2") (pintype "passive"))
      (node (ref "C63") (pin "2") (pinfunction "2_2") (pintype "passive"))
      (node (ref "C64") (pin "2") (pinfunction "2_2") (pintype "passive"))
      (node (ref "C65") (pin "2") (pinfunction "2_2") (pintype "passive"))
      (node (ref "C66") (pin "2") (pinfunction "2_2") (pintype "passive"))
      (node (ref "C67") (pin "2") (pinfunction "2_2") (pintype "passive"))
      (node (ref "C68") (pin "2") (pinfunction "2_2") (pintype "passive"))
      (node (ref "C69") (pin "2") (pinfunction "2_2") (pintype "passive"))
      (node (ref "C7") (pin "2") (pinfunction "2_2") (pintype "passive"))
      (node (ref "C70") (pin "2") (pinfunction "2_2") (pintype "passive"))
      (node (ref "C71") (pin "2") (pinfunction "2_2") (pintype "passive"))
      (node (ref "C72") (pin "2") (pinfunction "2_2") (pintype "passive"))
      (node (ref "C73") (pin "2") (pinfunction "2_2") (pintype "passive"))
      (node (ref "C74") (pin "2") (pinfunction "2_2") (pintype "passive"))
      (node (ref "C75") (pin "2") (pinfunction "2_2") (pintype "passive"))
      (node (ref "C76") (pin "2") (pinfunction "2_2") (pintype "passive"))
      (node (ref "C77") (pin "2") (pinfunction "2_2") (pintype "passive"))
      (node (ref "C78") (pin "2") (pinfunction "2_2") (pintype "passive"))
      (node (ref "C79") (pin "2") (pinfunction "2_2") (pintype "passive"))
      (node (ref "C8") (pin "2") (pinfunction "2_2") (pintype "passive"))
      (node (ref "C80") (pin "2") (pinfunction "2_2") (pintype "passive"))
      (node (ref "C81") (pin "2") (pinfunction "2_2") (pintype "passive"))
      (node (ref "C82") (pin "2") (pinfunction "2_2") (pintype "passive"))
      (node (ref "C83") (pin "2") (pinfunction "2_2") (pintype "passive"))
      (node (ref "C84") (pin "2") (pinfunction "2_2") (pintype "passive"))
      (node (ref "C85") (pin "2") (pinfunction "2_2") (pintype "passive"))
      (node (ref "C86") (pin "2") (pinfunction "2_2") (pintype "passive"))
      (node (ref "C87") (pin "2") (pinfunction "2_2") (pintype "passive"))
      (node (ref "C88") (pin "2") (pinfunction "2_2") (pintype "passive"))
      (node (ref "C89") (pin "2") (pinfunction "2_2") (pintype "passive"))
      (node (ref "C9") (pin "2") (pinfunction "2_2") (pintype "passive"))
      (node (ref "C90") (pin "2") (pinfunction "2_2") (pintype "passive"))
      (node (ref "C91") (pin "2") (pinfunction "2_2") (pintype "passive"))
      (node (ref "C92") (pin "2") (pinfunction "2_2") (pintype "passive"))
      (node (ref "C93") (pin "2") (pinfunction "2_2") (pintype "passive"))
      (node (ref "C94") (pin "2") (pinfunction "2_2") (pintype "passive"))
      (node (ref "C95") (pin "2") (pinfunction "2_2") (pintype "passive"))
      (node (ref "C96") (pin "2") (pinfunction "2_2") (pintype "passive"))
      (node (ref "C97") (pin "2") (pinfunction "2_2") (pintype "passive"))
      (node (ref "C98") (pin "2") (pinfunction "2_2") (pintype "passive"))
      (node (ref "C99") (pin "2") (pinfunction "2_2") (pintype "passive"))
      (node (ref "C_S1") (pin "2") (pinfunction "2_2") (pintype "passive"))
      (node (ref "C_S2") (pin "2") (pinfunction "2_2") (pintype "passive"))
      (node (ref "C_S3") (pin "2") (pinfunction "2_2") (pintype "passive"))
      (node (ref "C_S4") (pin "2") (pinfunction "2_2") (pintype "passive"))
      (node (ref "C_S5") (pin "2") (pinfunction "2_2") (pintype "passive"))
      (node (ref "IC1") (pin "22") (pinfunction "GND_22") (pintype "power_in"))
      (node (ref "IC1") (pin "8") (pinfunction "GND_8") (pintype "power_in"))
      (node (ref "L1") (pin "3-GND") (pinfunction "GND_3-GND") (pintype "bidirectional"))
      (node (ref "L10") (pin "3-GND") (pinfunction "GND_3-GND") (pintype "bidirectional"))
      (node (ref "L100") (pin "3-GND") (pinfunction "GND_3-GND") (pintype "bidirectional"))
      (node (ref "L101") (pin "3-GND") (pinfunction "GND_3-GND") (pintype "bidirectional"))
      (node (ref "L102") (pin "3-GND") (pinfunction "GND_3-GND") (pintype "bidirectional"))
      (node (ref "L103") (pin "3-GND") (pinfunction "GND_3-GND") (pintype "bidirectional"))
      (node (ref "L104") (pin "3-GND") (pinfunction "GND_3-GND") (pintype "bidirectional"))
      (node (ref "L105") (pin "3-GND") (pinfunction "GND_3-GND") (pintype "bidirectional"))
      (node (ref "L106") (pin "3-GND") (pinfunction "GND_3-GND") (pintype "bidirectional"))
      (node (ref "L107") (pin "3-GND") (pinfunction "GND_3-GND") (pintype "bidirectional"))
      (node (ref "L108") (pin "3-GND") (pinfunction "GND_3-GND") (pintype "bidirectional"))
      (node (ref "L109") (pin "3-GND") (pinfunction "GND_3-GND") (pintype "bidirectional"))
      (node (ref "L11") (pin "3-GND") (pinfunction "GND_3-GND") (pintype "bidirectional"))
      (node (ref "L110") (pin "3-GND") (pinfunction "GND_3-GND") (pintype "bidirectional"))
      (node (ref "L12") (pin "3-GND") (pinfunction "GND_3-GND") (pintype "bidirectional"))
      (node (ref "L13") (pin "3-GND") (pinfunction "GND_3-GND") (pintype "bidirectional"))
      (node (ref "L14") (pin "3-GND") (pinfunction "GND_3-GND") (pintype "bidirectional"))
      (node (ref "L15") (pin "3-GND") (pinfunction "GND_3-GND") (pintype "bidirectional"))
      (node (ref "L16") (pin "3-GND") (pinfunction "GND_3-GND") (pintype "bidirectional"))
      (node (ref "L17") (pin "3-GND") (pinfunction "GND_3-GND") (pintype "bidirectional"))
      (node (ref "L18") (pin "3-GND") (pinfunction "GND_3-GND") (pintype "bidirectional"))
      (node (ref "L19") (pin "3-GND") (pinfunction "GND_3-GND") (pintype "bidirectional"))
      (node (ref "L2") (pin "3-GND") (pinfunction "GND_3-GND") (pintype "bidirectional"))
      (node (ref "L20") (pin "3-GND") (pinfunction "GND_3-GND") (pintype "bidirectional"))
      (node (ref "L21") (pin "3-GND") (pinfunction "GND_3-GND") (pintype "bidirectional"))
      (node (ref "L22") (pin "3-GND") (pinfunction "GND_3-GND") (pintype "bidirectional"))
      (node (ref "L23") (pin "3-GND") (pinfunction "GND_3-GND") (pintype "bidirectional"))
      (node (ref "L24") (pin "3-GND") (pinfunction "GND_3-GND") (pintype "bidirectional"))
      (node (ref "L25") (pin "3-GND") (pinfunction "GND_3-GND") (pintype "bidirectional"))
      (node (ref "L26") (pin "3-GND") (pinfunction "GND_3-GND") (pintype "bidirectional"))
      (node (ref "L27") (pin "3-GND") (pinfunction "GND_3-GND") (pintype "bidirectional"))
      (node (ref "L28") (pin "3-GND") (pinfunction "GND_3-GND") (pintype "bidirectional"))
      (node (ref "L29") (pin "3-GND") (pinfunction "GND_3-GND") (pintype "bidirectional"))
      (node (ref "L3") (pin "3-GND") (pinfunction "GND_3-GND") (pintype "bidirectional"))
      (node (ref "L30") (pin "3-GND") (pinfunction "GND_3-GND") (pintype "bidirectional"))
      (node (ref "L31") (pin "3-GND") (pinfunction "GND_3-GND") (pintype "bidirectional"))
      (node (ref "L32") (pin "3-GND") (pinfunction "GND_3-GND") (pintype "bidirectional"))
      (node (ref "L33") (pin "3-GND") (pinfunction "GND_3-GND") (pintype "bidirectional"))
      (node (ref "L34") (pin "3-GND") (pinfunction "GND_3-GND") (pintype "bidirectional"))
      (node (ref "L35") (pin "3-GND") (pinfunction "GND_3-GND") (pintype "bidirectional"))
      (node (ref "L36") (pin "3-GND") (pinfunction "GND_3-GND") (pintype "bidirectional"))
      (node (ref "L37") (pin "3-GND") (pinfunction "GND_3-GND") (pintype "bidirectional"))
      (node (ref "L38") (pin "3-GND") (pinfunction "GND_3-GND") (pintype "bidirectional"))
      (node (ref "L39") (pin "3-GND") (pinfunction "GND_3-GND") (pintype "bidirectional"))
      (node (ref "L4") (pin "3-GND") (pinfunction "GND_3-GND") (pintype "bidirectional"))
      (node (ref "L40") (pin "3-GND") (pinfunction "GND_3-GND") (pintype "bidirectional"))
      (node (ref "L41") (pin "3-GND") (pinfunction "GND_3-GND") (pintype "bidirectional"))
      (node (ref "L42") (pin "3-GND") (pinfunction "GND_3-GND") (pintype "bidirectional"))
      (node (ref "L43") (pin "3-GND") (pinfunction "GND_3-GND") (pintype "bidirectional"))
      (node (ref "L44") (pin "3-GND") (pinfunction "GND_3-GND") (pintype "bidirectional"))
      (node (ref "L45") (pin "3-GND") (pinfunction "GND_3-GND") (pintype "bidirectional"))
      (node (ref "L46") (pin "3-GND") (pinfunction "GND_3-GND") (pintype "bidirectional"))
      (node (ref "L47") (pin "3-GND") (pinfunction "GND_3-GND") (pintype "bidirectional"))
      (node (ref "L48") (pin "3-GND") (pinfunction "GND_3-GND") (pintype "bidirectional"))
      (node (ref "L49") (pin "3-GND") (pinfunction "GND_3-GND") (pintype "bidirectional"))
      (node (ref "L5") (pin "3-GND") (pinfunction "GND_3-GND") (pintype "bidirectional"))
      (node (ref "L50") (pin "3-GND") (pinfunction "GND_3-GND") (pintype "bidirectional"))
      (node (ref "L51") (pin "3-GND") (pinfunction "GND_3-GND") (pintype "bidirectional"))
      (node (ref "L52") (pin "3-GND") (pinfunction "GND_3-GND") (pintype "bidirectional"))
      (node (ref "L53") (pin "3-GND") (pinfunction "GND_3-GND") (pintype "bidirectional"))
      (node (ref "L54") (pin "3-GND") (pinfunction "GND_3-GND") (pintype "bidirectional"))
      (node (ref "L55") (pin "3-GND") (pinfunction "GND_3-GND") (pintype "bidirectional"))
      (node (ref "L56") (pin "3-GND") (pinfunction "GND_3-GND") (pintype "bidirectional"))
      (node (ref "L57") (pin "3-GND") (pinfunction "GND_3-GND") (pintype "bidirectional"))
      (node (ref "L58") (pin "3-GND") (pinfunction "GND_3-GND") (pintype "bidirectional"))
      (node (ref "L59") (pin "3-GND") (pinfunction "GND_3-GND") (pintype "bidirectional"))
      (node (ref "L6") (pin "3-GND") (pinfunction "GND_3-GND") (pintype "bidirectional"))
      (node (ref "L60") (pin "3-GND") (pinfunction "GND_3-GND") (pintype "bidirectional"))
      (node (ref "L61") (pin "3-GND") (pinfunction "GND_3-GND") (pintype "bidirectional"))
      (node (ref "L62") (pin "3-GND") (pinfunction "GND_3-GND") (pintype "bidirectional"))
      (node (ref "L63") (pin "3-GND") (pinfunction "GND_3-GND") (pintype "bidirectional"))
      (node (ref "L64") (pin "3-GND") (pinfunction "GND_3-GND") (pintype "bidirectional"))
      (node (ref "L65") (pin "3-GND") (pinfunction "GND_3-GND") (pintype "bidirectional"))
      (node (ref "L66") (pin "3-GND") (pinfunction "GND_3-GND") (pintype "bidirectional"))
      (node (ref "L67") (pin "3-GND") (pinfunction "GND_3-GND") (pintype "bidirectional"))
      (node (ref "L68") (pin "3-GND") (pinfunction "GND_3-GND") (pintype "bidirectional"))
      (node (ref "L69") (pin "3-GND") (pinfunction "GND_3-GND") (pintype "bidirectional"))
      (node (ref "L7") (pin "3-GND") (pinfunction "GND_3-GND") (pintype "bidirectional"))
      (node (ref "L70") (pin "3-GND") (pinfunction "GND_3-GND") (pintype "bidirectional"))
      (node (ref "L71") (pin "3-GND") (pinfunction "GND_3-GND") (pintype "bidirectional"))
      (node (ref "L72") (pin "3-GND") (pinfunction "GND_3-GND") (pintype "bidirectional"))
      (node (ref "L73") (pin "3-GND") (pinfunction "GND_3-GND") (pintype "bidirectional"))
      (node (ref "L74") (pin "3-GND") (pinfunction "GND_3-GND") (pintype "bidirectional"))
      (node (ref "L75") (pin "3-GND") (pinfunction "GND_3-GND") (pintype "bidirectional"))
      (node (ref "L76") (pin "3-GND") (pinfunction "GND_3-GND") (pintype "bidirectional"))
      (node (ref "L77") (pin "3-GND") (pinfunction "GND_3-GND") (pintype "bidirectional"))
      (node (ref "L78") (pin "3-GND") (pinfunction "GND_3-GND") (pintype "bidirectional"))
      (node (ref "L79") (pin "3-GND") (pinfunction "GND_3-GND") (pintype "bidirectional"))
      (node (ref "L8") (pin "3-GND") (pinfunction "GND_3-GND") (pintype "bidirectional"))
      (node (ref "L80") (pin "3-GND") (pinfunction "GND_3-GND") (pintype "bidirectional"))
      (node (ref "L81") (pin "3-GND") (pinfunction "GND_3-GND") (pintype "bidirectional"))
      (node (ref "L82") (pin "3-GND") (pinfunction "GND_3-GND") (pintype "bidirectional"))
      (node (ref "L83") (pin "3-GND") (pinfunction "GND_3-GND") (pintype "bidirectional"))
      (node (ref "L84") (pin "3-GND") (pinfunction "GND_3-GND") (pintype "bidirectional"))
      (node (ref "L85") (pin "3-GND") (pinfunction "GND_3-GND") (pintype "bidirectional"))
      (node (ref "L86") (pin "3-GND") (pinfunction "GND_3-GND") (pintype "bidirectional"))
      (node (ref "L87") (pin "3-GND") (pinfunction "GND_3-GND") (pintype "bidirectional"))
      (node (ref "L88") (pin "3-GND") (pinfunction "GND_3-GND") (pintype "bidirectional"))
      (node (ref "L89") (pin "3-GND") (pinfunction "GND_3-GND") (pintype "bidirectional"))
      (node (ref "L9") (pin "3-GND") (pinfunction "GND_3-GND") (pintype "bidirectional"))
      (node (ref "L90") (pin "3-GND") (pinfunction "GND_3-GND") (pintype "bidirectional"))
      (node (ref "L91") (pin "3-GND") (pinfunction "GND_3-GND") (pintype "bidirectional"))
      (node (ref "L92") (pin "3-GND") (pinfunction "GND_3-GND") (pintype "bidirectional"))
      (node (ref "L93") (pin "3-GND") (pinfunction "GND_3-GND") (pintype "bidirectional"))
      (node (ref "L94") (pin "3-GND") (pinfunction "GND_3-GND") (pintype "bidirectional"))
      (node (ref "L95") (pin "3-GND") (pinfunction "GND_3-GND") (pintype "bidirectional"))
      (node (ref "L96") (pin "3-GND") (pinfunction "GND_3-GND") (pintype "bidirectional"))
      (node (ref "L97") (pin "3-GND") (pinfunction "GND_3-GND") (pintype "bidirectional"))
      (node (ref "L98") (pin "3-GND") (pinfunction "GND_3-GND") (pintype "bidirectional"))
      (node (ref "L99") (pin "3-GND") (pinfunction "GND_3-GND") (pintype "bidirectional"))
      (node (ref "PAD4") (pin "1") (pinfunction "P_1") (pintype "passive"))
      (node (ref "R_PHOTO") (pin "1") (pinfunction "1_1") (pintype "passive"))
      (node (ref "S+1") (pin "4") (pinfunction "GND_4") (pintype "bidirectional"))
      (node (ref "S1") (pin "3") (pinfunction "P_3") (pintype "passive"))
      (node (ref "S1") (pin "4") (pinfunction "P1_4") (pintype "passive"))
      (node (ref "S2") (pin "3") (pinfunction "P_3") (pintype "passive"))
      (node (ref "S2") (pin "4") (pinfunction "P1_4") (pintype "passive"))
      (node (ref "S3") (pin "3") (pinfunction "P_3") (pintype "passive"))
      (node (ref "S3") (pin "4") (pinfunction "P1_4") (pintype "passive"))
      (node (ref "S4") (pin "3") (pinfunction "P_3") (pintype "passive"))
      (node (ref "S4") (pin "4") (pinfunction "P1_4") (pintype "passive"))
      (node (ref "S5") (pin "3") (pinfunction "P_3") (pintype "passive"))
      (node (ref "S5") (pin "4") (pinfunction "P1_4") (pintype "passive"))
      (node (ref "SV1") (pin "6") (pinfunction "6_6") (pintype "passive"))
      (node (ref "U$1") (pin "5") (pinfunction "5_5") (pintype "input"))
    )
    (net (code "4") (name "INTA") (class "Default")
      (node (ref "IC1") (pin "5") (pinfunction "PD3(INT1)_5") (pintype "bidirectional"))
      (node (ref "PULLUP_INTA") (pin "1") (pinfunction "1_1") (pintype "passive"))
      (node (ref "S+1") (pin "3") (pinfunction "~{INTA}_3") (pintype "bidirectional"))
    )
    (net (code "5") (name "INTB") (class "Default")
      (node (ref "BRIDGE_INTB") (pin "1") (pinfunction "1_1") (pintype "passive"))
      (node (ref "IC1") (pin "4") (pinfunction "PD2(INT0)_4") (pintype "bidirectional"))
    )
    (net (code "6") (name "LEDALARM") (class "Default")
      (node (ref "IC1") (pin "26") (pinfunction "PC3(ADC3)_26") (pintype "bidirectional"))
      (node (ref "LEDAL") (pin "C") (pinfunction "C_C") (pintype "passive"))
    )
    (net (code "7") (name "LEDMIN1") (class "Default")
      (node (ref "IC1") (pin "18") (pinfunction "PB4(MISO)_18") (pintype "bidirectional"))
      (node (ref "LED1") (pin "C") (pinfunction "C_C") (pintype "passive"))
      (node (ref "SV1") (pin "1") (pinfunction "1_1") (pintype "passive"))
    )
    (net (code "8") (name "LEDMIN2") (class "Default")
      (node (ref "BRIDGE_MOSI") (pin "2") (pinfunction "2_2") (pintype "passive"))
      (node (ref "IC1") (pin "17") (pinfunction "PB3(MOSI/OC2)_17") (pintype "bidirectional"))
      (node (ref "LED2") (pin "C") (pinfunction "C_C") (pintype "passive"))
    )
    (net (code "9") (name "LEDMIN3") (class "Default")
      (node (ref "IC1") (pin "15") (pinfunction "PB1(OC1A)_15") (pintype "bidirectional"))
      (node (ref "LED3") (pin "C") (pinfunction "C_C") (pintype "passive"))
    )
    (net (code "10") (name "LEDMIN4") (class "Default")
      (node (ref "BRIDGE_SCK") (pin "2") (pinfunction "2_2") (pintype "passive"))
      (node (ref "IC1") (pin "19") (pinfunction "PB5(SCK)_19") (pintype "bidirectional"))
      (node (ref "LED4") (pin "C") (pinfunction "C_C") (pintype "passive"))
    )
    (net (code "11") (name "MATRIXIN") (class "Default")
      (node (ref "IC1") (pin "2") (pinfunction "PD0(RXD)_2") (pintype "bidirectional"))
      (node (ref "R_MATRIXIN") (pin "1") (pinfunction "1_1") (pintype "passive"))
    )
    (net (code "12") (name "MATRIXOUT") (class "Default")
      (node (ref "L110") (pin "2-DOUT") (pinfunction "DOUT_2-DOUT") (pintype "output"))
    )
    (net (code "13") (name "NC1") (class "Default")
      (node (ref "IC1") (pin "23") (pinfunction "PC0(ADC0)_23") (pintype "bidirectional"))
      (node (ref "PAD2") (pin "1") (pinfunction "P_1") (pintype "passive"))
    )
    (net (code "14") (name "NC2") (class "Default")
      (node (ref "IC1") (pin "6") (pinfunction "PD4(XCK/T0)_6") (pintype "bidirectional"))
      (node (ref "PAD1") (pin "1") (pinfunction "P_1") (pintype "passive"))
    )
    (net (code "15") (name "Net-(BRIDGE_MOSI-Pad1)") (class "Default")
      (node (ref "BRIDGE_MOSI") (pin "1") (pinfunction "1_1") (pintype "passive"))
      (node (ref "SV1") (pin "4") (pinfunction "4_4") (pintype "passive"))
    )
    (net (code "16") (name "Net-(BRIDGE_RESET2-Pad1)") (class "Default")
      (node (ref "BRIDGE_RESET2") (pin "1") (pinfunction "1_1") (pintype "passive"))
      (node (ref "SV1") (pin "5") (pinfunction "5_5") (pintype "passive"))
    )
    (net (code "17") (name "Net-(BRIDGE_SCK-Pad1)") (class "Default")
      (node (ref "BRIDGE_SCK") (pin "1") (pinfunction "1_1") (pintype "passive"))
      (node (ref "SV1") (pin "3") (pinfunction "3_3") (pintype "passive"))
    )
    (net (code "18") (name "Net-(IC1-AREF)") (class "Default")
      (node (ref "C119") (pin "2") (pinfunction "2_2") (pintype "passive"))
      (node (ref "IC1") (pin "21") (pinfunction "AREF_21") (pintype "passive"))
    )
    (net (code "19") (name "Net-(IC1-AVCC)") (class "Default")
      (node (ref "C118") (pin "2") (pinfunction "2_2") (pintype "passive"))
      (node (ref "IC1") (pin "20") (pinfunction "AVCC_20") (pintype "power_in"))
      (node (ref "L111") (pin "2") (pinfunction "2_2") (pintype "passive"))
    )
    (net (code "20") (name "Net-(IC1-PB6(XTAL1{slash}TOSC1))") (class "Default")
      (node (ref "C117") (pin "2") (pinfunction "2_2") (pintype "passive"))
      (node (ref "IC1") (pin "9") (pinfunction "PB6(XTAL1/TOSC1)_9") (pintype "bidirectional"))
      (node (ref "Q2") (pin "1") (pinfunction "1_1") (pintype "passive"))
    )
    (net (code "21") (name "Net-(IC1-PB7(XTAL2{slash}TOSC2))") (class "Default")
      (node (ref "C116") (pin "2") (pinfunction "2_2") (pintype "passive"))
      (node (ref "IC1") (pin "10") (pinfunction "PB7(XTAL2/TOSC2)_10") (pintype "bidirectional"))
      (node (ref "Q2") (pin "2") (pinfunction "2_2") (pintype "passive"))
    )
    (net (code "22") (name "Net-(IC1-PC1(ADC1))") (class "Default")
      (node (ref "IC1") (pin "24") (pinfunction "PC1(ADC1)_24") (pintype "bidirectional"))
      (node (ref "R_MOSFET") (pin "1") (pinfunction "1_1") (pintype "passive"))
    )
    (net (code "23") (name "Net-(IC1-PC6({slash}RESET))") (class "Default")
      (node (ref "BRIDGE_RESET1") (pin "1") (pinfunction "1_1") (pintype "passive"))
      (node (ref "IC1") (pin "1") (pinfunction "PC6(/RESET)_1") (pintype "bidirectional"))
      (node (ref "R_RESET") (pin "1") (pinfunction "1_1") (pintype "passive"))
    )
    (net (code "24") (name "Net-(L1-DIN)") (class "Default")
      (node (ref "L1") (pin "4-DIN") (pinfunction "DIN_4-DIN") (pintype "input"))
      (node (ref "R_MATRIXIN") (pin "2") (pinfunction "2_2") (pintype "passive"))
    )
    (net (code "25") (name "Net-(L1-DOUT)") (class "Default")
      (node (ref "L1") (pin "2-DOUT") (pinfunction "DOUT_2-DOUT") (pintype "output"))
      (node (ref "L2") (pin "4-DIN") (pinfunction "DIN_4-DIN") (pintype "input"))
    )
    (net (code "26") (name "Net-(L2-DOUT)") (class "Default")
      (node (ref "L2") (pin "2-DOUT") (pinfunction "DOUT_2-DOUT") (pintype "output"))
      (node (ref "L3") (pin "4-DIN") (pinfunction "DIN_4-DIN") (pintype "input"))
    )
    (net (code "27") (name "Net-(L3-DOUT)") (class "Default")
      (node (ref "L3") (pin "2-DOUT") (pinfunction "DOUT_2-DOUT") (pintype "output"))
      (node (ref "L4") (pin "4-DIN") (pinfunction "DIN_4-DIN") (pintype "input"))
    )
    (net (code "28") (name "Net-(L4-DOUT)") (class "Default")
      (node (ref "L4") (pin "2-DOUT") (pinfunction "DOUT_2-DOUT") (pintype "output"))
      (node (ref "L5") (pin "4-DIN") (pinfunction "DIN_4-DIN") (pintype "input"))
    )
    (net (code "29") (name "Net-(L5-DOUT)") (class "Default")
      (node (ref "L5") (pin "2-DOUT") (pinfunction "DOUT_2-DOUT") (pintype "output"))
      (node (ref "L6") (pin "4-DIN") (pinfunction "DIN_4-DIN") (pintype "input"))
    )
    (net (code "30") (name "Net-(L6-DOUT)") (class "Default")
      (node (ref "L6") (pin "2-DOUT") (pinfunction "DOUT_2-DOUT") (pintype "output"))
      (node (ref "L7") (pin "4-DIN") (pinfunction "DIN_4-DIN") (pintype "input"))
    )
    (net (code "31") (name "Net-(L7-DOUT)") (class "Default")
      (node (ref "L7") (pin "2-DOUT") (pinfunction "DOUT_2-DOUT") (pintype "output"))
      (node (ref "L8") (pin "4-DIN") (pinfunction "DIN_4-DIN") (pintype "input"))
    )
    (net (code "32") (name "Net-(L8-DOUT)") (class "Default")
      (node (ref "L8") (pin "2-DOUT") (pinfunction "DOUT_2-DOUT") (pintype "output"))
      (node (ref "L9") (pin "4-DIN") (pinfunction "DIN_4-DIN") (pintype "input"))
    )
    (net (code "33") (name "Net-(L10-DIN)") (class "Default")
      (node (ref "L10") (pin "4-DIN") (pinfunction "DIN_4-DIN") (pintype "input"))
      (node (ref "L9") (pin "2-DOUT") (pinfunction "DOUT_2-DOUT") (pintype "output"))
    )
    (net (code "34") (name "Net-(L10-DOUT)") (class "Default")
      (node (ref "L10") (pin "2-DOUT") (pinfunction "DOUT_2-DOUT") (pintype "output"))
      (node (ref "L11") (pin "4-DIN") (pinfunction "DIN_4-DIN") (pintype "input"))
    )
    (net (code "35") (name "Net-(L11-DOUT)") (class "Default")
      (node (ref "L11") (pin "2-DOUT") (pinfunction "DOUT_2-DOUT") (pintype "output"))
      (node (ref "L12") (pin "4-DIN") (pinfunction "DIN_4-DIN") (pintype "input"))
    )
    (net (code "36") (name "Net-(L12-DOUT)") (class "Default")
      (node (ref "L12") (pin "2-DOUT") (pinfunction "DOUT_2-DOUT") (pintype "output"))
      (node (ref "L13") (pin "4-DIN") (pinfunction "DIN_4-DIN") (pintype "input"))
    )
    (net (code "37") (name "Net-(L13-DOUT)") (class "Default")
      (node (ref "L13") (pin "2-DOUT") (pinfunction "DOUT_2-DOUT") (pintype "output"))
      (node (ref "L14") (pin "4-DIN") (pinfunction "DIN_4-DIN") (pintype "input"))
    )
    (net (code "38") (name "Net-(L14-DOUT)") (class "Default")
      (node (ref "L14") (pin "2-DOUT") (pinfunction "DOUT_2-DOUT") (pintype "output"))
      (node (ref "L15") (pin "4-DIN") (pinfunction "DIN_4-DIN") (pintype "input"))
    )
    (net (code "39") (name "Net-(L15-DOUT)") (class "Default")
      (node (ref "L15") (pin "2-DOUT") (pinfunction "DOUT_2-DOUT") (pintype "output"))
      (node (ref "L16") (pin "4-DIN") (pinfunction "DIN_4-DIN") (pintype "input"))
    )
    (net (code "40") (name "Net-(L16-DOUT)") (class "Default")
      (node (ref "L16") (pin "2-DOUT") (pinfunction "DOUT_2-DOUT") (pintype "output"))
      (node (ref "L17") (pin "4-DIN") (pinfunction "DIN_4-DIN") (pintype "input"))
    )
    (net (code "41") (name "Net-(L17-DOUT)") (class "Default")
      (node (ref "L17") (pin "2-DOUT") (pinfunction "DOUT_2-DOUT") (pintype "output"))
      (node (ref "L18") (pin "4-DIN") (pinfunction "DIN_4-DIN") (pintype "input"))
    )
    (net (code "42") (name "Net-(L18-DOUT)") (class "Default")
      (node (ref "L18") (pin "2-DOUT") (pinfunction "DOUT_2-DOUT") (pintype "output"))
      (node (ref "L19") (pin "4-DIN") (pinfunction "DIN_4-DIN") (pintype "input"))
    )
    (net (code "43") (name "Net-(L19-DOUT)") (class "Default")
      (node (ref "L19") (pin "2-DOUT") (pinfunction "DOUT_2-DOUT") (pintype "output"))
      (node (ref "L20") (pin "4-DIN") (pinfunction "DIN_4-DIN") (pintype "input"))
    )
    (net (code "44") (name "Net-(L20-DOUT)") (class "Default")
      (node (ref "L20") (pin "2-DOUT") (pinfunction "DOUT_2-DOUT") (pintype "output"))
      (node (ref "L21") (pin "4-DIN") (pinfunction "DIN_4-DIN") (pintype "input"))
    )
    (net (code "45") (name "Net-(L21-DOUT)") (class "Default")
      (node (ref "L21") (pin "2-DOUT") (pinfunction "DOUT_2-DOUT") (pintype "output"))
      (node (ref "L22") (pin "4-DIN") (pinfunction "DIN_4-DIN") (pintype "input"))
    )
    (net (code "46") (name "Net-(L22-DOUT)") (class "Default")
      (node (ref "L22") (pin "2-DOUT") (pinfunction "DOUT_2-DOUT") (pintype "output"))
      (node (ref "L23") (pin "4-DIN") (pinfunction "DIN_4-DIN") (pintype "input"))
    )
    (net (code "47") (name "Net-(L23-DOUT)") (class "Default")
      (node (ref "L23") (pin "2-DOUT") (pinfunction "DOUT_2-DOUT") (pintype "output"))
      (node (ref "L24") (pin "4-DIN") (pinfunction "DIN_4-DIN") (pintype "input"))
    )
    (net (code "48") (name "Net-(L24-DOUT)") (class "Default")
      (node (ref "L24") (pin "2-DOUT") (pinfunction "DOUT_2-DOUT") (pintype "output"))
      (node (ref "L25") (pin "4-DIN") (pinfunction "DIN_4-DIN") (pintype "input"))
    )
    (net (code "49") (name "Net-(L25-DOUT)") (class "Default")
      (node (ref "L25") (pin "2-DOUT") (pinfunction "DOUT_2-DOUT") (pintype "output"))
      (node (ref "L26") (pin "4-DIN") (pinfunction "DIN_4-DIN") (pintype "input"))
    )
    (net (code "50") (name "Net-(L26-DOUT)") (class "Default")
      (node (ref "L26") (pin "2-DOUT") (pinfunction "DOUT_2-DOUT") (pintype "output"))
      (node (ref "L27") (pin "4-DIN") (pinfunction "DIN_4-DIN") (pintype "input"))
    )
    (net (code "51") (name "Net-(L27-DOUT)") (class "Default")
      (node (ref "L27") (pin "2-DOUT") (pinfunction "DOUT_2-DOUT") (pintype "output"))
      (node (ref "L28") (pin "4-DIN") (pinfunction "DIN_4-DIN") (pintype "input"))
    )
    (net (code "52") (name "Net-(L28-DOUT)") (class "Default")
      (node (ref "L28") (pin "2-DOUT") (pinfunction "DOUT_2-DOUT") (pintype "output"))
      (node (ref "L29") (pin "4-DIN") (pinfunction "DIN_4-DIN") (pintype "input"))
    )
    (net (code "53") (name "Net-(L29-DOUT)") (class "Default")
      (node (ref "L29") (pin "2-DOUT") (pinfunction "DOUT_2-DOUT") (pintype "output"))
      (node (ref "L30") (pin "4-DIN") (pinfunction "DIN_4-DIN") (pintype "input"))
    )
    (net (code "54") (name "Net-(L30-DOUT)") (class "Default")
      (node (ref "L30") (pin "2-DOUT") (pinfunction "DOUT_2-DOUT") (pintype "output"))
      (node (ref "L31") (pin "4-DIN") (pinfunction "DIN_4-DIN") (pintype "input"))
    )
    (net (code "55") (name "Net-(L31-DOUT)") (class "Default")
      (node (ref "L31") (pin "2-DOUT") (pinfunction "DOUT_2-DOUT") (pintype "output"))
      (node (ref "L32") (pin "4-DIN") (pinfunction "DIN_4-DIN") (pintype "input"))
    )
    (net (code "56") (name "Net-(L32-DOUT)") (class "Default")
      (node (ref "L32") (pin "2-DOUT") (pinfunction "DOUT_2-DOUT") (pintype "output"))
      (node (ref "L33") (pin "4-DIN") (pinfunction "DIN_4-DIN") (pintype "input"))
    )
    (net (code "57") (name "Net-(L33-DOUT)") (class "Default")
      (node (ref "L33") (pin "2-DOUT") (pinfunction "DOUT_2-DOUT") (pintype "output"))
      (node (ref "L34") (pin "4-DIN") (pinfunction "DIN_4-DIN") (pintype "input"))
    )
    (net (code "58") (name "Net-(L34-DOUT)") (class "Default")
      (node (ref "L34") (pin "2-DOUT") (pinfunction "DOUT_2-DOUT") (pintype "output"))
      (node (ref "L35") (pin "4-DIN") (pinfunction "DIN_4-DIN") (pintype "input"))
    )
    (net (code "59") (name "Net-(L35-DOUT)") (class "Default")
      (node (ref "L35") (pin "2-DOUT") (pinfunction "DOUT_2-DOUT") (pintype "output"))
      (node (ref "L36") (pin "4-DIN") (pinfunction "DIN_4-DIN") (pintype "input"))
    )
    (net (code "60") (name "Net-(L36-DOUT)") (class "Default")
      (node (ref "L36") (pin "2-DOUT") (pinfunction "DOUT_2-DOUT") (pintype "output"))
      (node (ref "L37") (pin "4-DIN") (pinfunction "DIN_4-DIN") (pintype "input"))
    )
    (net (code "61") (name "Net-(L37-DOUT)") (class "Default")
      (node (ref "L37") (pin "2-DOUT") (pinfunction "DOUT_2-DOUT") (pintype "output"))
      (node (ref "L38") (pin "4-DIN") (pinfunction "DIN_4-DIN") (pintype "input"))
    )
    (net (code "62") (name "Net-(L38-DOUT)") (class "Default")
      (node (ref "L38") (pin "2-DOUT") (pinfunction "DOUT_2-DOUT") (pintype "output"))
      (node (ref "L39") (pin "4-DIN") (pinfunction "DIN_4-DIN") (pintype "input"))
    )
    (net (code "63") (name "Net-(L39-DOUT)") (class "Default")
      (node (ref "L39") (pin "2-DOUT") (pinfunction "DOUT_2-DOUT") (pintype "output"))
      (node (ref "L40") (pin "4-DIN") (pinfunction "DIN_4-DIN") (pintype "input"))
    )
    (net (code "64") (name "Net-(L40-DOUT)") (class "Default")
      (node (ref "L40") (pin "2-DOUT") (pinfunction "DOUT_2-DOUT") (pintype "output"))
      (node (ref "L41") (pin "4-DIN") (pinfunction "DIN_4-DIN") (pintype "input"))
    )
    (net (code "65") (name "Net-(L41-DOUT)") (class "Default")
      (node (ref "L41") (pin "2-DOUT") (pinfunction "DOUT_2-DOUT") (pintype "output"))
      (node (ref "L42") (pin "4-DIN") (pinfunction "DIN_4-DIN") (pintype "input"))
    )
    (net (code "66") (name "Net-(L42-DOUT)") (class "Default")
      (node (ref "L42") (pin "2-DOUT") (pinfunction "DOUT_2-DOUT") (pintype "output"))
      (node (ref "L43") (pin "4-DIN") (pinfunction "DIN_4-DIN") (pintype "input"))
    )
    (net (code "67") (name "Net-(L43-DOUT)") (class "Default")
      (node (ref "L43") (pin "2-DOUT") (pinfunction "DOUT_2-DOUT") (pintype "output"))
      (node (ref "L44") (pin "4-DIN") (pinfunction "DIN_4-DIN") (pintype "input"))
    )
    (net (code "68") (name "Net-(L44-DOUT)") (class "Default")
      (node (ref "L44") (pin "2-DOUT") (pinfunction "DOUT_2-DOUT") (pintype "output"))
      (node (ref "L45") (pin "4-DIN") (pinfunction "DIN_4-DIN") (pintype "input"))
    )
    (net (code "69") (name "Net-(L45-DOUT)") (class "Default")
      (node (ref "L45") (pin "2-DOUT") (pinfunction "DOUT_2-DOUT") (pintype "output"))
      (node (ref "L46") (pin "4-DIN") (pinfunction "DIN_4-DIN") (pintype "input"))
    )
    (net (code "70") (name "Net-(L46-DOUT)") (class "Default")
      (node (ref "L46") (pin "2-DOUT") (pinfunction "DOUT_2-DOUT") (pintype "output"))
      (node (ref "L47") (pin "4-DIN") (pinfunction "DIN_4-DIN") (pintype "input"))
    )
    (net (code "71") (name "Net-(L47-DOUT)") (class "Default")
      (node (ref "L47") (pin "2-DOUT") (pinfunction "DOUT_2-DOUT") (pintype "output"))
      (node (ref "L48") (pin "4-DIN") (pinfunction "DIN_4-DIN") (pintype "input"))
    )
    (net (code "72") (name "Net-(L48-DOUT)") (class "Default")
      (node (ref "L48") (pin "2-DOUT") (pinfunction "DOUT_2-DOUT") (pintype "output"))
      (node (ref "L49") (pin "4-DIN") (pinfunction "DIN_4-DIN") (pintype "input"))
    )
    (net (code "73") (name "Net-(L49-DOUT)") (class "Default")
      (node (ref "L49") (pin "2-DOUT") (pinfunction "DOUT_2-DOUT") (pintype "output"))
      (node (ref "L50") (pin "4-DIN") (pinfunction "DIN_4-DIN") (pintype "input"))
    )
    (net (code "74") (name "Net-(L50-DOUT)") (class "Default")
      (node (ref "L50") (pin "2-DOUT") (pinfunction "DOUT_2-DOUT") (pintype "output"))
      (node (ref "L51") (pin "4-DIN") (pinfunction "DIN_4-DIN") (pintype "input"))
    )
    (net (code "75") (name "Net-(L51-DOUT)") (class "Default")
      (node (ref "L51") (pin "2-DOUT") (pinfunction "DOUT_2-DOUT") (pintype "output"))
      (node (ref "L52") (pin "4-DIN") (pinfunction "DIN_4-DIN") (pintype "input"))
    )
    (net (code "76") (name "Net-(L52-DOUT)") (class "Default")
      (node (ref "L52") (pin "2-DOUT") (pinfunction "DOUT_2-DOUT") (pintype "output"))
      (node (ref "L53") (pin "4-DIN") (pinfunction "DIN_4-DIN") (pintype "input"))
    )
    (net (code "77") (name "Net-(L53-DOUT)") (class "Default")
      (node (ref "L53") (pin "2-DOUT") (pinfunction "DOUT_2-DOUT") (pintype "output"))
      (node (ref "L54") (pin "4-DIN") (pinfunction "DIN_4-DIN") (pintype "input"))
    )
    (net (code "78") (name "Net-(L54-DOUT)") (class "Default")
      (node (ref "L54") (pin "2-DOUT") (pinfunction "DOUT_2-DOUT") (pintype "output"))
      (node (ref "L55") (pin "4-DIN") (pinfunction "DIN_4-DIN") (pintype "input"))
    )
    (net (code "79") (name "Net-(L55-DOUT)") (class "Default")
      (node (ref "L55") (pin "2-DOUT") (pinfunction "DOUT_2-DOUT") (pintype "output"))
      (node (ref "L56") (pin "4-DIN") (pinfunction "DIN_4-DIN") (pintype "input"))
    )
    (net (code "80") (name "Net-(L56-DOUT)") (class "Default")
      (node (ref "L56") (pin "2-DOUT") (pinfunction "DOUT_2-DOUT") (pintype "output"))
      (node (ref "L57") (pin "4-DIN") (pinfunction "DIN_4-DIN") (pintype "input"))
    )
    (net (code "81") (name "Net-(L57-DOUT)") (class "Default")
      (node (ref "L57") (pin "2-DOUT") (pinfunction "DOUT_2-DOUT") (pintype "output"))
      (node (ref "L58") (pin "4-DIN") (pinfunction "DIN_4-DIN") (pintype "input"))
    )
    (net (code "82") (name "Net-(L58-DOUT)") (class "Default")
      (node (ref "L58") (pin "2-DOUT") (pinfunction "DOUT_2-DOUT") (pintype "output"))
      (node (ref "L59") (pin "4-DIN") (pinfunction "DIN_4-DIN") (pintype "input"))
    )
    (net (code "83") (name "Net-(L59-DOUT)") (class "Default")
      (node (ref "L59") (pin "2-DOUT") (pinfunction "DOUT_2-DOUT") (pintype "output"))
      (node (ref "L60") (pin "4-DIN") (pinfunction "DIN_4-DIN") (pintype "input"))
    )
    (net (code "84") (name "Net-(L60-DOUT)") (class "Default")
      (node (ref "L60") (pin "2-DOUT") (pinfunction "DOUT_2-DOUT") (pintype "output"))
      (node (ref "L61") (pin "4-DIN") (pinfunction "DIN_4-DIN") (pintype "input"))
    )
    (net (code "85") (name "Net-(L61-DOUT)") (class "Default")
      (node (ref "L61") (pin "2-DOUT") (pinfunction "DOUT_2-DOUT") (pintype "output"))
      (node (ref "L62") (pin "4-DIN") (pinfunction "DIN_4-DIN") (pintype "input"))
    )
    (net (code "86") (name "Net-(L62-DOUT)") (class "Default")
      (node (ref "L62") (pin "2-DOUT") (pinfunction "DOUT_2-DOUT") (pintype "output"))
      (node (ref "L63") (pin "4-DIN") (pinfunction "DIN_4-DIN") (pintype "input"))
    )
    (net (code "87") (name "Net-(L63-DOUT)") (class "Default")
      (node (ref "L63") (pin "2-DOUT") (pinfunction "DOUT_2-DOUT") (pintype "output"))
      (node (ref "L64") (pin "4-DIN") (pinfunction "DIN_4-DIN") (pintype "input"))
    )
    (net (code "88") (name "Net-(L64-DOUT)") (class "Default")
      (node (ref "L64") (pin "2-DOUT") (pinfunction "DOUT_2-DOUT") (pintype "output"))
      (node (ref "L65") (pin "4-DIN") (pinfunction "DIN_4-DIN") (pintype "input"))
    )
    (net (code "89") (name "Net-(L65-DOUT)") (class "Default")
      (node (ref "L65") (pin "2-DOUT") (pinfunction "DOUT_2-DOUT") (pintype "output"))
      (node (ref "L66") (pin "4-DIN") (pinfunction "DIN_4-DIN") (pintype "input"))
    )
    (net (code "90") (name "Net-(L66-DOUT)") (class "Default")
      (node (ref "L66") (pin "2-DOUT") (pinfunction "DOUT_2-DOUT") (pintype "output"))
      (node (ref "L67") (pin "4-DIN") (pinfunction "DIN_4-DIN") (pintype "input"))
    )
    (net (code "91") (name "Net-(L67-DOUT)") (class "Default")
      (node (ref "L67") (pin "2-DOUT") (pinfunction "DOUT_2-DOUT") (pintype "output"))
      (node (ref "L68") (pin "4-DIN") (pinfunction "DIN_4-DIN") (pintype "input"))
    )
    (net (code "92") (name "Net-(L68-DOUT)") (class "Default")
      (node (ref "L68") (pin "2-DOUT") (pinfunction "DOUT_2-DOUT") (pintype "output"))
      (node (ref "L69") (pin "4-DIN") (pinfunction "DIN_4-DIN") (pintype "input"))
    )
    (net (code "93") (name "Net-(L69-DOUT)") (class "Default")
      (node (ref "L69") (pin "2-DOUT") (pinfunction "DOUT_2-DOUT") (pintype "output"))
      (node (ref "L70") (pin "4-DIN") (pinfunction "DIN_4-DIN") (pintype "input"))
    )
    (net (code "94") (name "Net-(L70-DOUT)") (class "Default")
      (node (ref "L70") (pin "2-DOUT") (pinfunction "DOUT_2-DOUT") (pintype "output"))
      (node (ref "L71") (pin "4-DIN") (pinfunction "DIN_4-DIN") (pintype "input"))
    )
    (net (code "95") (name "Net-(L71-DOUT)") (class "Default")
      (node (ref "L71") (pin "2-DOUT") (pinfunction "DOUT_2-DOUT") (pintype "output"))
      (node (ref "L72") (pin "4-DIN") (pinfunction "DIN_4-DIN") (pintype "input"))
    )
    (net (code "96") (name "Net-(L72-DOUT)") (class "Default")
      (node (ref "L72") (pin "2-DOUT") (pinfunction "DOUT_2-DOUT") (pintype "output"))
      (node (ref "L73") (pin "4-DIN") (pinfunction "DIN_4-DIN") (pintype "input"))
    )
    (net (code "97") (name "Net-(L73-DOUT)") (class "Default")
      (node (ref "L73") (pin "2-DOUT") (pinfunction "DOUT_2-DOUT") (pintype "output"))
      (node (ref "L74") (pin "4-DIN") (pinfunction "DIN_4-DIN") (pintype "input"))
    )
    (net (code "98") (name "Net-(L74-DOUT)") (class "Default")
      (node (ref "L74") (pin "2-DOUT") (pinfunction "DOUT_2-DOUT") (pintype "output"))
      (node (ref "L75") (pin "4-DIN") (pinfunction "DIN_4-DIN") (pintype "input"))
    )
    (net (code "99") (name "Net-(L75-DOUT)") (class "Default")
      (node (ref "L75") (pin "2-DOUT") (pinfunction "DOUT_2-DOUT") (pintype "output"))
      (node (ref "L76") (pin "4-DIN") (pinfunction "DIN_4-DIN") (pintype "input"))
    )
    (net (code "100") (name "Net-(L76-DOUT)") (class "Default")
      (node (ref "L76") (pin "2-DOUT") (pinfunction "DOUT_2-DOUT") (pintype "output"))
      (node (ref "L77") (pin "4-DIN") (pinfunction "DIN_4-DIN") (pintype "input"))
    )
    (net (code "101") (name "Net-(L77-DOUT)") (class "Default")
      (node (ref "L77") (pin "2-DOUT") (pinfunction "DOUT_2-DOUT") (pintype "output"))
      (node (ref "L78") (pin "4-DIN") (pinfunction "DIN_4-DIN") (pintype "input"))
    )
    (net (code "102") (name "Net-(L78-DOUT)") (class "Default")
      (node (ref "L78") (pin "2-DOUT") (pinfunction "DOUT_2-DOUT") (pintype "output"))
      (node (ref "L79") (pin "4-DIN") (pinfunction "DIN_4-DIN") (pintype "input"))
    )
    (net (code "103") (name "Net-(L79-DOUT)") (class "Default")
      (node (ref "L79") (pin "2-DOUT") (pinfunction "DOUT_2-DOUT") (pintype "output"))
      (node (ref "L80") (pin "4-DIN") (pinfunction "DIN_4-DIN") (pintype "input"))
    )
    (net (code "104") (name "Net-(L80-DOUT)") (class "Default")
      (node (ref "L80") (pin "2-DOUT") (pinfunction "DOUT_2-DOUT") (pintype "output"))
      (node (ref "L81") (pin "4-DIN") (pinfunction "DIN_4-DIN") (pintype "input"))
    )
    (net (code "105") (name "Net-(L81-DOUT)") (class "Default")
      (node (ref "L81") (pin "2-DOUT") (pinfunction "DOUT_2-DOUT") (pintype "output"))
      (node (ref "L82") (pin "4-DIN") (pinfunction "DIN_4-DIN") (pintype "input"))
    )
    (net (code "106") (name "Net-(L82-DOUT)") (class "Default")
      (node (ref "L82") (pin "2-DOUT") (pinfunction "DOUT_2-DOUT") (pintype "output"))
      (node (ref "L83") (pin "4-DIN") (pinfunction "DIN_4-DIN") (pintype "input"))
    )
    (net (code "107") (name "Net-(L83-DOUT)") (class "Default")
      (node (ref "L83") (pin "2-DOUT") (pinfunction "DOUT_2-DOUT") (pintype "output"))
      (node (ref "L84") (pin "4-DIN") (pinfunction "DIN_4-DIN") (pintype "input"))
    )
    (net (code "108") (name "Net-(L84-DOUT)") (class "Default")
      (node (ref "L84") (pin "2-DOUT") (pinfunction "DOUT_2-DOUT") (pintype "output"))
      (node (ref "L85") (pin "4-DIN") (pinfunction "DIN_4-DIN") (pintype "input"))
    )
    (net (code "109") (name "Net-(L85-DOUT)") (class "Default")
      (node (ref "L85") (pin "2-DOUT") (pinfunction "DOUT_2-DOUT") (pintype "output"))
      (node (ref "L86") (pin "4-DIN") (pinfunction "DIN_4-DIN") (pintype "input"))
    )
    (net (code "110") (name "Net-(L86-DOUT)") (class "Default")
      (node (ref "L86") (pin "2-DOUT") (pinfunction "DOUT_2-DOUT") (pintype "output"))
      (node (ref "L87") (pin "4-DIN") (pinfunction "DIN_4-DIN") (pintype "input"))
    )
    (net (code "111") (name "Net-(L87-DOUT)") (class "Default")
      (node (ref "L87") (pin "2-DOUT") (pinfunction "DOUT_2-DOUT") (pintype "output"))
      (node (ref "L88") (pin "4-DIN") (pinfunction "DIN_4-DIN") (pintype "input"))
    )
    (net (code "112") (name "Net-(L88-DOUT)") (class "Default")
      (node (ref "L88") (pin "2-DOUT") (pinfunction "DOUT_2-DOUT") (pintype "output"))
      (node (ref "L89") (pin "4-DIN") (pinfunction "DIN_4-DIN") (pintype "input"))
    )
    (net (code "113") (name "Net-(L89-DOUT)") (class "Default")
      (node (ref "L89") (pin "2-DOUT") (pinfunction "DOUT_2-DOUT") (pintype "output"))
      (node (ref "L90") (pin "4-DIN") (pinfunction "DIN_4-DIN") (pintype "input"))
    )
    (net (code "114") (name "Net-(L90-DOUT)") (class "Default")
      (node (ref "L90") (pin "2-DOUT") (pinfunction "DOUT_2-DOUT") (pintype "output"))
      (node (ref "L91") (pin "4-DIN") (pinfunction "DIN_4-DIN") (pintype "input"))
    )
    (net (code "115") (name "Net-(L91-DOUT)") (class "Default")
      (node (ref "L91") (pin "2-DOUT") (pinfunction "DOUT_2-DOUT") (pintype "output"))
      (node (ref "L92") (pin "4-DIN") (pinfunction "DIN_4-DIN") (pintype "input"))
    )
    (net (code "116") (name "Net-(L92-DOUT)") (class "Default")
      (node (ref "L92") (pin "2-DOUT") (pinfunction "DOUT_2-DOUT") (pintype "output"))
      (node (ref "L93") (pin "4-DIN") (pinfunction "DIN_4-DIN") (pintype "input"))
    )
    (net (code "117") (name "Net-(L93-DOUT)") (class "Default")
      (node (ref "L93") (pin "2-DOUT") (pinfunction "DOUT_2-DOUT") (pintype "output"))
      (node (ref "L94") (pin "4-DIN") (pinfunction "DIN_4-DIN") (pintype "input"))
    )
    (net (code "118") (name "Net-(L94-DOUT)") (class "Default")
      (node (ref "L94") (pin "2-DOUT") (pinfunction "DOUT_2-DOUT") (pintype "output"))
      (node (ref "L95") (pin "4-DIN") (pinfunction "DIN_4-DIN") (pintype "input"))
    )
    (net (code "119") (name "Net-(L95-DOUT)") (class "Default")
      (node (ref "L95") (pin "2-DOUT") (pinfunction "DOUT_2-DOUT") (pintype "output"))
      (node (ref "L96") (pin "4-DIN") (pinfunction "DIN_4-DIN") (pintype "input"))
    )
    (net (code "120") (name "Net-(L96-DOUT)") (class "Default")
      (node (ref "L96") (pin "2-DOUT") (pinfunction "DOUT_2-DOUT") (pintype "output"))
      (node (ref "L97") (pin "4-DIN") (pinfunction "DIN_4-DIN") (pintype "input"))
    )
    (net (code "121") (name "Net-(L97-DOUT)") (class "Default")
      (node (ref "L97") (pin "2-DOUT") (pinfunction "DOUT_2-DOUT") (pintype "output"))
      (node (ref "L98") (pin "4-DIN") (pinfunction "DIN_4-DIN") (pintype "input"))
    )
    (net (code "122") (name "Net-(L98-DOUT)") (class "Default")
      (node (ref "L98") (pin "2-DOUT") (pinfunction "DOUT_2-DOUT") (pintype "output"))
      (node (ref "L99") (pin "4-DIN") (pinfunction "DIN_4-DIN") (pintype "input"))
    )
    (net (code "123") (name "Net-(L100-DIN)") (class "Default")
      (node (ref "L100") (pin "4-DIN") (pinfunction "DIN_4-DIN") (pintype "input"))
      (node (ref "L99") (pin "2-DOUT") (pinfunction "DOUT_2-DOUT") (pintype "output"))
    )
    (net (code "124") (name "Net-(L100-DOUT)") (class "Default")
      (node (ref "L100") (pin "2-DOUT") (pinfunction "DOUT_2-DOUT") (pintype "output"))
      (node (ref "L101") (pin "4-DIN") (pinfunction "DIN_4-DIN") (pintype "input"))
    )
    (net (code "125") (name "Net-(L101-DOUT)") (class "Default")
      (node (ref "L101") (pin "2-DOUT") (pinfunction "DOUT_2-DOUT") (pintype "output"))
      (node (ref "L102") (pin "4-DIN") (pinfunction "DIN_4-DIN") (pintype "input"))
    )
    (net (code "126") (name "Net-(L102-DOUT)") (class "Default")
      (node (ref "L102") (pin "2-DOUT") (pinfunction "DOUT_2-DOUT") (pintype "output"))
      (node (ref "L103") (pin "4-DIN") (pinfunction "DIN_4-DIN") (pintype "input"))
    )
    (net (code "127") (name "Net-(L103-DOUT)") (class "Default")
      (node (ref "L103") (pin "2-DOUT") (pinfunction "DOUT_2-DOUT") (pintype "output"))
      (node (ref "L104") (pin "4-DIN") (pinfunction "DIN_4-DIN") (pintype "input"))
    )
    (net (code "128") (name "Net-(L104-DOUT)") (class "Default")
      (node (ref "L104") (pin "2-DOUT") (pinfunction "DOUT_2-DOUT") (pintype "output"))
      (node (ref "L105") (pin "4-DIN") (pinfunction "DIN_4-DIN") (pintype "input"))
    )
    (net (code "129") (name "Net-(L105-DOUT)") (class "Default")
      (node (ref "L105") (pin "2-DOUT") (pinfunction "DOUT_2-DOUT") (pintype "output"))
      (node (ref "L106") (pin "4-DIN") (pinfunction "DIN_4-DIN") (pintype "input"))
    )
    (net (code "130") (name "Net-(L106-DOUT)") (class "Default")
      (node (ref "L106") (pin "2-DOUT") (pinfunction "DOUT_2-DOUT") (pintype "output"))
      (node (ref "L107") (pin "4-DIN") (pinfunction "DIN_4-DIN") (pintype "input"))
    )
    (net (code "131") (name "Net-(L107-DOUT)") (class "Default")
      (node (ref "L107") (pin "2-DOUT") (pinfunction "DOUT_2-DOUT") (pintype "output"))
      (node (ref "L108") (pin "4-DIN") (pinfunction "DIN_4-DIN") (pintype "input"))
    )
    (net (code "132") (name "Net-(L108-DOUT)") (class "Default")
      (node (ref "L108") (pin "2-DOUT") (pinfunction "DOUT_2-DOUT") (pintype "output"))
      (node (ref "L109") (pin "4-DIN") (pinfunction "DIN_4-DIN") (pintype "input"))
    )
    (net (code "133") (name "Net-(L109-DOUT)") (class "Default")
      (node (ref "L109") (pin "2-DOUT") (pinfunction "DOUT_2-DOUT") (pintype "output"))
      (node (ref "L110") (pin "4-DIN") (pinfunction "DIN_4-DIN") (pintype "input"))
    )
    (net (code "134") (name "Net-(LED1-PadA)") (class "Default")
      (node (ref "LED1") (pin "A") (pinfunction "A_A") (pintype "passive"))
      (node (ref "R_LED1") (pin "2") (pinfunction "2_2") (pintype "passive"))
    )
    (net (code "135") (name "Net-(LED2-PadA)") (class "Default")
      (node (ref "LED2") (pin "A") (pinfunction "A_A") (pintype "passive"))
      (node (ref "R_LED2") (pin "2") (pinfunction "2_2") (pintype "passive"))
    )
    (net (code "136") (name "Net-(LED3-PadA)") (class "Default")
      (node (ref "LED3") (pin "A") (pinfunction "A_A") (pintype "passive"))
      (node (ref "R_LED3") (pin "2") (pinfunction "2_2") (pintype "passive"))
    )
    (net (code "137") (name "Net-(LED4-PadA)") (class "Default")
      (node (ref "LED4") (pin "A") (pinfunction "A_A") (pintype "passive"))
      (node (ref "R_LED4") (pin "2") (pinfunction "2_2") (pintype "passive"))
    )
    (net (code "138") (name "Net-(LEDAL-PadA)") (class "Default")
      (node (ref "LEDAL") (pin "A") (pinfunction "A_A") (pintype "passive"))
      (node (ref "R_LEDAL") (pin "2") (pinfunction "2_2") (pintype "passive"))
    )
    (net (code "139") (name "Net-(Q3-G)") (class "Default")
      (node (ref "Q3") (pin "1") (pinfunction "G_1") (pintype "passive"))
      (node (ref "R_MOSFET") (pin "2") (pinfunction "2_2") (pintype "passive"))
    )
    (net (code "140") (name "Net-(S+1-SCL)") (class "Default")
      (node (ref "PULLUP_SCL") (pin "1") (pinfunction "1_1") (pintype "passive"))
      (node (ref "R_SCL") (pin "2") (pinfunction "2_2") (pintype "passive"))
      (node (ref "S+1") (pin "6") (pinfunction "SCL_6") (pintype "bidirectional"))
    )
    (net (code "141") (name "Net-(S+1-SDA)") (class "Default")
      (node (ref "PULLUP_SDA") (pin "1") (pinfunction "1_1") (pintype "passive"))
      (node (ref "R_SDA") (pin "2") (pinfunction "2_2") (pintype "passive"))
      (node (ref "S+1") (pin "5") (pinfunction "SDA_5") (pintype "bidirectional"))
    )
    (net (code "142") (name "Net-(S+1-SQW{slash}~{INTB})") (class "Default")
      (node (ref "BRIDGE_INTB") (pin "2") (pinfunction "2_2") (pintype "passive"))
      (node (ref "PULLUP_INTB") (pin "1") (pinfunction "1_1") (pintype "passive"))
      (node (ref "S+1") (pin "7") (pinfunction "SQW/~{INTB}_7") (pintype "bidirectional"))
    )
    (net (code "143") (name "Net-(S+1-X1)") (class "Default")
      (node (ref "Q_DS") (pin "1") (pinfunction "1_1") (pintype "passive"))
      (node (ref "S+1") (pin "1") (pinfunction "X1_1") (pintype "bidirectional"))
    )
    (net (code "144") (name "Net-(S+1-X2)") (class "Default")
      (node (ref "Q_DS") (pin "2") (pinfunction "2_2") (pintype "passive"))
      (node (ref "S+1") (pin "2") (pinfunction "X2_2") (pintype "bidirectional"))
    )
    (net (code "145") (name "Net-(S1-S)") (class "Default")
      (node (ref "R_S1") (pin "1") (pinfunction "1_1") (pintype "passive"))
      (node (ref "S1") (pin "1") (pinfunction "S_1") (pintype "passive"))
      (node (ref "S1") (pin "2") (pinfunction "S1_2") (pintype "passive"))
    )
    (net (code "146") (name "Net-(S2-S)") (class "Default")
      (node (ref "R_S2") (pin "1") (pinfunction "1_1") (pintype "passive"))
      (node (ref "S2") (pin "1") (pinfunction "S_1") (pintype "passive"))
    )
    (net (code "147") (name "Net-(S3-S)") (class "Default")
      (node (ref "R_S3") (pin "1") (pinfunction "1_1") (pintype "passive"))
      (node (ref "S3") (pin "1") (pinfunction "S_1") (pintype "passive"))
    )
    (net (code "148") (name "Net-(S4-S)") (class "Default")
      (node (ref "R_S4") (pin "1") (pinfunction "1_1") (pintype "passive"))
      (node (ref "S4") (pin "1") (pinfunction "S_1") (pintype "passive"))
    )
    (net (code "149") (name "Net-(S5-S)") (class "Default")
      (node (ref "R_S5") (pin "1") (pinfunction "1_1") (pintype "passive"))
      (node (ref "S5") (pin "1") (pinfunction "S_1") (pintype "passive"))
    )
    (net (code "150") (name "PHOTO") (class "Default")
      (node (ref "IC1") (pin "25") (pinfunction "PC2(ADC2)_25") (pintype "bidirectional"))
      (node (ref "LDR") (pin "1") (pinfunction "1_1") (pintype "passive"))
      (node (ref "R_PHOTO") (pin "2") (pinfunction "2_2") (pintype "passive"))
    )
    (net (code "151") (name "RESET") (class "Default")
      (node (ref "BRIDGE_RESET1") (pin "2") (pinfunction "2_2") (pintype "passive"))
      (node (ref "BRIDGE_RESET2") (pin "2") (pinfunction "2_2") (pintype "passive"))
    )
    (net (code "152") (name "SCHALTER1") (class "Default")
      (node (ref "C_S1") (pin "1") (pinfunction "1_1") (pintype "passive"))
      (node (ref "IC1") (pin "3") (pinfunction "PD1(TXD)_3") (pintype "bidirectional"))
      (node (ref "R_S1") (pin "2") (pinfunction "2_2") (pintype "passive"))
    )
    (net (code "153") (name "SCHALTER2") (class "Default")
      (node (ref "C_S2") (pin "1") (pinfunction "1_1") (pintype "passive"))
      (node (ref "IC1") (pin "12") (pinfunction "PD6(AIN0)_12") (pintype "bidirectional"))
      (node (ref "R_S2") (pin "2") (pinfunction "2_2") (pintype "passive"))
    )
    (net (code "154") (name "SCHALTER3") (class "Default")
      (node (ref "C_S3") (pin "1") (pinfunction "1_1") (pintype "passive"))
      (node (ref "IC1") (pin "11") (pinfunction "PD5(T1)_11") (pintype "bidirectional"))
      (node (ref "R_S3") (pin "2") (pinfunction "2_2") (pintype "passive"))
    )
    (net (code "155") (name "SCHALTER4") (class "Default")
      (node (ref "C_S4") (pin "1") (pinfunction "1_1") (pintype "passive"))
      (node (ref "IC1") (pin "13") (pinfunction "PD7(AIN1)_13") (pintype "bidirectional"))
      (node (ref "R_S4") (pin "2") (pinfunction "2_2") (pintype "passive"))
    )
    (net (code "156") (name "SCHALTER5") (class "Default")
      (node (ref "C_S5") (pin "1") (pinfunction "1_1") (pintype "passive"))
      (node (ref "IC1") (pin "14") (pinfunction "PB0(ICP)_14") (pintype "bidirectional"))
      (node (ref "R_S5") (pin "2") (pinfunction "2_2") (pintype "passive"))
    )
    (net (code "157") (name "SCL") (class "Default")
      (node (ref "IC1") (pin "28") (pinfunction "PC5(ADC5/SCL)_28") (pintype "bidirectional"))
      (node (ref "R_SCL") (pin "1") (pinfunction "1_1") (pintype "passive"))
    )
    (net (code "158") (name "SDA") (class "Default")
      (node (ref "IC1") (pin "27") (pinfunction "PC4(ADC4/SDA)_27") (pintype "bidirectional"))
      (node (ref "R_SDA") (pin "1") (pinfunction "1_1") (pintype "passive"))
    )
    (net (code "159") (name "VDD") (class "Default")
      (node (ref "BRIDGE_VDD") (pin "1") (pinfunction "1_1") (pintype "passive"))
      (node (ref "BRIDGE_VDD") (pin "2") (pinfunction "2_2") (pintype "passive"))
      (node (ref "C1") (pin "1") (pinfunction "1_1") (pintype "passive"))
      (node (ref "C10") (pin "1") (pinfunction "1_1") (pintype "passive"))
      (node (ref "C100") (pin "1") (pinfunction "1_1") (pintype "passive"))
      (node (ref "C101") (pin "1") (pinfunction "1_1") (pintype "passive"))
      (node (ref "C102") (pin "1") (pinfunction "1_1") (pintype "passive"))
      (node (ref "C103") (pin "1") (pinfunction "1_1") (pintype "passive"))
      (node (ref "C104") (pin "1") (pinfunction "1_1") (pintype "passive"))
      (node (ref "C105") (pin "1") (pinfunction "1_1") (pintype "passive"))
      (node (ref "C106") (pin "1") (pinfunction "1_1") (pintype "passive"))
      (node (ref "C107") (pin "1") (pinfunction "1_1") (pintype "passive"))
      (node (ref "C108") (pin "1") (pinfunction "1_1") (pintype "passive"))
      (node (ref "C109") (pin "1") (pinfunction "1_1") (pintype "passive"))
      (node (ref "C11") (pin "1") (pinfunction "1_1") (pintype "passive"))
      (node (ref "C110") (pin "1") (pinfunction "1_1") (pintype "passive"))
      (node (ref "C12") (pin "1") (pinfunction "1_1") (pintype "passive"))
      (node (ref "C13") (pin "1") (pinfunction "1_1") (pintype "passive"))
      (node (ref "C14") (pin "1") (pinfunction "1_1") (pintype "passive"))
      (node (ref "C15") (pin "1") (pinfunction "1_1") (pintype "passive"))
      (node (ref "C16") (pin "1") (pinfunction "1_1") (pintype "passive"))
      (node (ref "C17") (pin "1") (pinfunction "1_1") (pintype "passive"))
      (node (ref "C18") (pin "1") (pinfunction "1_1") (pintype "passive"))
      (node (ref "C19") (pin "1") (pinfunction "1_1") (pintype "passive"))
      (node (ref "C2") (pin "1") (pinfunction "1_1") (pintype "passive"))
      (node (ref "C20") (pin "1") (pinfunction "1_1") (pintype "passive"))
      (node (ref "C21") (pin "1") (pinfunction "1_1") (pintype "passive"))
      (node (ref "C22") (pin "1") (pinfunction "1_1") (pintype "passive"))
      (node (ref "C23") (pin "1") (pinfunction "1_1") (pintype "passive"))
      (node (ref "C24") (pin "1") (pinfunction "1_1") (pintype "passive"))
      (node (ref "C25") (pin "1") (pinfunction "1_1") (pintype "passive"))
      (node (ref "C26") (pin "1") (pinfunction "1_1") (pintype "passive"))
      (node (ref "C27") (pin "1") (pinfunction "1_1") (pintype "passive"))
      (node (ref "C28") (pin "1") (pinfunction "1_1") (pintype "passive"))
      (node (ref "C29") (pin "1") (pinfunction "1_1") (pintype "passive"))
      (node (ref "C3") (pin "1") (pinfunction "1_1") (pintype "passive"))
      (node (ref "C30") (pin "1") (pinfunction "1_1") (pintype "passive"))
      (node (ref "C31") (pin "1") (pinfunction "1_1") (pintype "passive"))
      (node (ref "C32") (pin "1") (pinfunction "1_1") (pintype "passive"))
      (node (ref "C33") (pin "1") (pinfunction "1_1") (pintype "passive"))
      (node (ref "C34") (pin "1") (pinfunction "1_1") (pintype "passive"))
      (node (ref "C35") (pin "1") (pinfunction "1_1") (pintype "passive"))
      (node (ref "C36") (pin "1") (pinfunction "1_1") (pintype "passive"))
      (node (ref "C37") (pin "1") (pinfunction "1_1") (pintype "passive"))
      (node (ref "C38") (pin "1") (pinfunction "1_1") (pintype "passive"))
      (node (ref "C39") (pin "1") (pinfunction "1_1") (pintype "passive"))
      (node (ref "C4") (pin "1") (pinfunction "1_1") (pintype "passive"))
      (node (ref "C40") (pin "1") (pinfunction "1_1") (pintype "passive"))
      (node (ref "C41") (pin "1") (pinfunction "1_1") (pintype "passive"))
      (node (ref "C42") (pin "1") (pinfunction "1_1") (pintype "passive"))
      (node (ref "C43") (pin "1") (pinfunction "1_1") (pintype "passive"))
      (node (ref "C44") (pin "1") (pinfunction "1_1") (pintype "passive"))
      (node (ref "C45") (pin "1") (pinfunction "1_1") (pintype "passive"))
      (node (ref "C46") (pin "1") (pinfunction "1_1") (pintype "passive"))
      (node (ref "C47") (pin "1") (pinfunction "1_1") (pintype "passive"))
      (node (ref "C48") (pin "1") (pinfunction "1_1") (pintype "passive"))
      (node (ref "C49") (pin "1") (pinfunction "1_1") (pintype "passive"))
      (node (ref "C5") (pin "1") (pinfunction "1_1") (pintype "passive"))
      (node (ref "C50") (pin "1") (pinfunction "1_1") (pintype "passive"))
      (node (ref "C51") (pin "1") (pinfunction "1_1") (pintype "passive"))
      (node (ref "C52") (pin "1") (pinfunction "1_1") (pintype "passive"))
      (node (ref "C53") (pin "1") (pinfunction "1_1") (pintype "passive"))
      (node (ref "C54") (pin "1") (pinfunction "1_1") (pintype "passive"))
      (node (ref "C55") (pin "1") (pinfunction "1_1") (pintype "passive"))
      (node (ref "C56") (pin "1") (pinfunction "1_1") (pintype "passive"))
      (node (ref "C57") (pin "1") (pinfunction "1_1") (pintype "passive"))
      (node (ref "C58") (pin "1") (pinfunction "1_1") (pintype "passive"))
      (node (ref "C59") (pin "1") (pinfunction "1_1") (pintype "passive"))
      (node (ref "C6") (pin "1") (pinfunction "1_1") (pintype "passive"))
      (node (ref "C60") (pin "1") (pinfunction "1_1") (pintype "passive"))
      (node (ref "C61") (pin "1") (pinfunction "1_1") (pintype "passive"))
      (node (ref "C62") (pin "1") (pinfunction "1_1") (pintype "passive"))
      (node (ref "C63") (pin "1") (pinfunction "1_1") (pintype "passive"))
      (node (ref "C64") (pin "1") (pinfunction "1_1") (pintype "passive"))
      (node (ref "C65") (pin "1") (pinfunction "1_1") (pintype "passive"))
      (node (ref "C66") (pin "1") (pinfunction "1_1") (pintype "passive"))
      (node (ref "C67") (pin "1") (pinfunction "1_1") (pintype "passive"))
      (node (ref "C68") (pin "1") (pinfunction "1_1") (pintype "passive"))
      (node (ref "C69") (pin "1") (pinfunction "1_1") (pintype "passive"))
      (node (ref "C7") (pin "1") (pinfunction "1_1") (pintype "passive"))
      (node (ref "C70") (pin "1") (pinfunction "1_1") (pintype "passive"))
      (node (ref "C71") (pin "1") (pinfunction "1_1") (pintype "passive"))
      (node (ref "C72") (pin "1") (pinfunction "1_1") (pintype "passive"))
      (node (ref "C73") (pin "1") (pinfunction "1_1") (pintype "passive"))
      (node (ref "C74") (pin "1") (pinfunction "1_1") (pintype "passive"))
      (node (ref "C75") (pin "1") (pinfunction "1_1") (pintype "passive"))
      (node (ref "C76") (pin "1") (pinfunction "1_1") (pintype "passive"))
      (node (ref "C77") (pin "1") (pinfunction "1_1") (pintype "passive"))
      (node (ref "C78") (pin "1") (pinfunction "1_1") (pintype "passive"))
      (node (ref "C79") (pin "1") (pinfunction "1_1") (pintype "passive"))
      (node (ref "C8") (pin "1") (pinfunction "1_1") (pintype "passive"))
      (node (ref "C80") (pin "1") (pinfunction "1_1") (pintype "passive"))
      (node (ref "C81") (pin "1") (pinfunction "1_1") (pintype "passive"))
      (node (ref "C82") (pin "1") (pinfunction "1_1") (pintype "passive"))
      (node (ref "C83") (pin "1") (pinfunction "1_1") (pintype "passive"))
      (node (ref "C84") (pin "1") (pinfunction "1_1") (pintype "passive"))
      (node (ref "C85") (pin "1") (pinfunction "1_1") (pintype "passive"))
      (node (ref "C86") (pin "1") (pinfunction "1_1") (pintype "passive"))
      (node (ref "C87") (pin "1") (pinfunction "1_1") (pintype "passive"))
      (node (ref "C88") (pin "1") (pinfunction "1_1") (pintype "passive"))
      (node (ref "C89") (pin "1") (pinfunction "1_1") (pintype "passive"))
      (node (ref "C9") (pin "1") (pinfunction "1_1") (pintype "passive"))
      (node (ref "C90") (pin "1") (pinfunction "1_1") (pintype "passive"))
      (node (ref "C91") (pin "1") (pinfunction "1_1") (pintype "passive"))
      (node (ref "C92") (pin "1") (pinfunction "1_1") (pintype "passive"))
      (node (ref "C93") (pin "1") (pinfunction "1_1") (pintype "passive"))
      (node (ref "C94") (pin "1") (pinfunction "1_1") (pintype "passive"))
      (node (ref "C95") (pin "1") (pinfunction "1_1") (pintype "passive"))
      (node (ref "C96") (pin "1") (pinfunction "1_1") (pintype "passive"))
      (node (ref "C97") (pin "1") (pinfunction "1_1") (pintype "passive"))
      (node (ref "C98") (pin "1") (pinfunction "1_1") (pintype "passive"))
      (node (ref "C99") (pin "1") (pinfunction "1_1") (pintype "passive"))
      (node (ref "L1") (pin "1-VDD") (pinfunction "VDD_1-VDD") (pintype "bidirectional"))
      (node (ref "L10") (pin "1-VDD") (pinfunction "VDD_1-VDD") (pintype "bidirectional"))
      (node (ref "L100") (pin "1-VDD") (pinfunction "VDD_1-VDD") (pintype "bidirectional"))
      (node (ref "L101") (pin "1-VDD") (pinfunction "VDD_1-VDD") (pintype "bidirectional"))
      (node (ref "L102") (pin "1-VDD") (pinfunction "VDD_1-VDD") (pintype "bidirectional"))
      (node (ref "L103") (pin "1-VDD") (pinfunction "VDD_1-VDD") (pintype "bidirectional"))
      (node (ref "L104") (pin "1-VDD") (pinfunction "VDD_1-VDD") (pintype "bidirectional"))
      (node (ref "L105") (pin "1-VDD") (pinfunction "VDD_1-VDD") (pintype "bidirectional"))
      (node (ref "L106") (pin "1-VDD") (pinfunction "VDD_1-VDD") (pintype "bidirectional"))
      (node (ref "L107") (pin "1-VDD") (pinfunction "VDD_1-VDD") (pintype "bidirectional"))
      (node (ref "L108") (pin "1-VDD") (pinfunction "VDD_1-VDD") (pintype "bidirectional"))
      (node (ref "L109") (pin "1-VDD") (pinfunction "VDD_1-VDD") (pintype "bidirectional"))
      (node (ref "L11") (pin "1-VDD") (pinfunction "VDD_1-VDD") (pintype "bidirectional"))
      (node (ref "L110") (pin "1-VDD") (pinfunction "VDD_1-VDD") (pintype "bidirectional"))
      (node (ref "L12") (pin "1-VDD") (pinfunction "VDD_1-VDD") (pintype "bidirectional"))
      (node (ref "L13") (pin "1-VDD") (pinfunction "VDD_1-VDD") (pintype "bidirectional"))
      (node (ref "L14") (pin "1-VDD") (pinfunction "VDD_1-VDD") (pintype "bidirectional"))
      (node (ref "L15") (pin "1-VDD") (pinfunction "VDD_1-VDD") (pintype "bidirectional"))
      (node (ref "L16") (pin "1-VDD") (pinfunction "VDD_1-VDD") (pintype "bidirectional"))
      (node (ref "L17") (pin "1-VDD") (pinfunction "VDD_1-VDD") (pintype "bidirectional"))
      (node (ref "L18") (pin "1-VDD") (pinfunction "VDD_1-VDD") (pintype "bidirectional"))
      (node (ref "L19") (pin "1-VDD") (pinfunction "VDD_1-VDD") (pintype "bidirectional"))
      (node (ref "L2") (pin "1-VDD") (pinfunction "VDD_1-VDD") (pintype "bidirectional"))
      (node (ref "L20") (pin "1-VDD") (pinfunction "VDD_1-VDD") (pintype "bidirectional"))
      (node (ref "L21") (pin "1-VDD") (pinfunction "VDD_1-VDD") (pintype "bidirectional"))
      (node (ref "L22") (pin "1-VDD") (pinfunction "VDD_1-VDD") (pintype "bidirectional"))
      (node (ref "L23") (pin "1-VDD") (pinfunction "VDD_1-VDD") (pintype "bidirectional"))
      (node (ref "L24") (pin "1-VDD") (pinfunction "VDD_1-VDD") (pintype "bidirectional"))
      (node (ref "L25") (pin "1-VDD") (pinfunction "VDD_1-VDD") (pintype "bidirectional"))
      (node (ref "L26") (pin "1-VDD") (pinfunction "VDD_1-VDD") (pintype "bidirectional"))
      (node (ref "L27") (pin "1-VDD") (pinfunction "VDD_1-VDD") (pintype "bidirectional"))
      (node (ref "L28") (pin "1-VDD") (pinfunction "VDD_1-VDD") (pintype "bidirectional"))
      (node (ref "L29") (pin "1-VDD") (pinfunction "VDD_1-VDD") (pintype "bidirectional"))
      (node (ref "L3") (pin "1-VDD") (pinfunction "VDD_1-VDD") (pintype "bidirectional"))
      (node (ref "L30") (pin "1-VDD") (pinfunction "VDD_1-VDD") (pintype "bidirectional"))
      (node (ref "L31") (pin "1-VDD") (pinfunction "VDD_1-VDD") (pintype "bidirectional"))
      (node (ref "L32") (pin "1-VDD") (pinfunction "VDD_1-VDD") (pintype "bidirectional"))
      (node (ref "L33") (pin "1-VDD") (pinfunction "VDD_1-VDD") (pintype "bidirectional"))
      (node (ref "L34") (pin "1-VDD") (pinfunction "VDD_1-VDD") (pintype "bidirectional"))
      (node (ref "L35") (pin "1-VDD") (pinfunction "VDD_1-VDD") (pintype "bidirectional"))
      (node (ref "L36") (pin "1-VDD") (pinfunction "VDD_1-VDD") (pintype "bidirectional"))
      (node (ref "L37") (pin "1-VDD") (pinfunction "VDD_1-VDD") (pintype "bidirectional"))
      (node (ref "L38") (pin "1-VDD") (pinfunction "VDD_1-VDD") (pintype "bidirectional"))
      (node (ref "L39") (pin "1-VDD") (pinfunction "VDD_1-VDD") (pintype "bidirectional"))
      (node (ref "L4") (pin "1-VDD") (pinfunction "VDD_1-VDD") (pintype "bidirectional"))
      (node (ref "L40") (pin "1-VDD") (pinfunction "VDD_1-VDD") (pintype "bidirectional"))
      (node (ref "L41") (pin "1-VDD") (pinfunction "VDD_1-VDD") (pintype "bidirectional"))
      (node (ref "L42") (pin "1-VDD") (pinfunction "VDD_1-VDD") (pintype "bidirectional"))
      (node (ref "L43") (pin "1-VDD") (pinfunction "VDD_1-VDD") (pintype "bidirectional"))
      (node (ref "L44") (pin "1-VDD") (pinfunction "VDD_1-VDD") (pintype "bidirectional"))
      (node (ref "L45") (pin "1-VDD") (pinfunction "VDD_1-VDD") (pintype "bidirectional"))
      (node (ref "L46") (pin "1-VDD") (pinfunction "VDD_1-VDD") (pintype "bidirectional"))
      (node (ref "L47") (pin "1-VDD") (pinfunction "VDD_1-VDD") (pintype "bidirectional"))
      (node (ref "L48") (pin "1-VDD") (pinfunction "VDD_1-VDD") (pintype "bidirectional"))
      (node (ref "L49") (pin "1-VDD") (pinfunction "VDD_1-VDD") (pintype "bidirectional"))
      (node (ref "L5") (pin "1-VDD") (pinfunction "VDD_1-VDD") (pintype "bidirectional"))
      (node (ref "L50") (pin "1-VDD") (pinfunction "VDD_1-VDD") (pintype "bidirectional"))
      (node (ref "L51") (pin "1-VDD") (pinfunction "VDD_1-VDD") (pintype "bidirectional"))
      (node (ref "L52") (pin "1-VDD") (pinfunction "VDD_1-VDD") (pintype "bidirectional"))
      (node (ref "L53") (pin "1-VDD") (pinfunction "VDD_1-VDD") (pintype "bidirectional"))
      (node (ref "L54") (pin "1-VDD") (pinfunction "VDD_1-VDD") (pintype "bidirectional"))
      (node (ref "L55") (pin "1-VDD") (pinfunction "VDD_1-VDD") (pintype "bidirectional"))
      (node (ref "L56") (pin "1-VDD") (pinfunction "VDD_1-VDD") (pintype "bidirectional"))
      (node (ref "L57") (pin "1-VDD") (pinfunction "VDD_1-VDD") (pintype "bidirectional"))
      (node (ref "L58") (pin "1-VDD") (pinfunction "VDD_1-VDD") (pintype "bidirectional"))
      (node (ref "L59") (pin "1-VDD") (pinfunction "VDD_1-VDD") (pintype "bidirectional"))
      (node (ref "L6") (pin "1-VDD") (pinfunction "VDD_1-VDD") (pintype "bidirectional"))
      (node (ref "L60") (pin "1-VDD") (pinfunction "VDD_1-VDD") (pintype "bidirectional"))
      (node (ref "L61") (pin "1-VDD") (pinfunction "VDD_1-VDD") (pintype "bidirectional"))
      (node (ref "L62") (pin "1-VDD") (pinfunction "VDD_1-VDD") (pintype "bidirectional"))
      (node (ref "L63") (pin "1-VDD") (pinfunction "VDD_1-VDD") (pintype "bidirectional"))
      (node (ref "L64") (pin "1-VDD") (pinfunction "VDD_1-VDD") (pintype "bidirectional"))
      (node (ref "L65") (pin "1-VDD") (pinfunction "VDD_1-VDD") (pintype "bidirectional"))
      (node (ref "L66") (pin "1-VDD") (pinfunction "VDD_1-VDD") (pintype "bidirectional"))
      (node (ref "L67") (pin "1-VDD") (pinfunction "VDD_1-VDD") (pintype "bidirectional"))
      (node (ref "L68") (pin "1-VDD") (pinfunction "VDD_1-VDD") (pintype "bidirectional"))
      (node (ref "L69") (pin "1-VDD") (pinfunction "VDD_1-VDD") (pintype "bidirectional"))
      (node (ref "L7") (pin "1-VDD") (pinfunction "VDD_1-VDD") (pintype "bidirectional"))
      (node (ref "L70") (pin "1-VDD") (pinfunction "VDD_1-VDD") (pintype "bidirectional"))
      (node (ref "L71") (pin "1-VDD") (pinfunction "VDD_1-VDD") (pintype "bidirectional"))
      (node (ref "L72") (pin "1-VDD") (pinfunction "VDD_1-VDD") (pintype "bidirectional"))
      (node (ref "L73") (pin "1-VDD") (pinfunction "VDD_1-VDD") (pintype "bidirectional"))
      (node (ref "L74") (pin "1-VDD") (pinfunction "VDD_1-VDD") (pintype "bidirectional"))
      (node (ref "L75") (pin "1-VDD") (pinfunction "VDD_1-VDD") (pintype "bidirectional"))
      (node (ref "L76") (pin "1-VDD") (pinfunction "VDD_1-VDD") (pintype "bidirectional"))
      (node (ref "L77") (pin "1-VDD") (pinfunction "VDD_1-VDD") (pintype "bidirectional"))
      (node (ref "L78") (pin "1-VDD") (pinfunction "VDD_1-VDD") (pintype "bidirectional"))
      (node (ref "L79") (pin "1-VDD") (pinfunction "VDD_1-VDD") (pintype "bidirectional"))
      (node (ref "L8") (pin "1-VDD") (pinfunction "VDD_1-VDD") (pintype "bidirectional"))
      (node (ref "L80") (pin "1-VDD") (pinfunction "VDD_1-VDD") (pintype "bidirectional"))
      (node (ref "L81") (pin "1-VDD") (pinfunction "VDD_1-VDD") (pintype "bidirectional"))
      (node (ref "L82") (pin "1-VDD") (pinfunction "VDD_1-VDD") (pintype "bidirectional"))
      (node (ref "L83") (pin "1-VDD") (pinfunction "VDD_1-VDD") (pintype "bidirectional"))
      (node (ref "L84") (pin "1-VDD") (pinfunction "VDD_1-VDD") (pintype "bidirectional"))
      (node (ref "L85") (pin "1-VDD") (pinfunction "VDD_1-VDD") (pintype "bidirectional"))
      (node (ref "L86") (pin "1-VDD") (pinfunction "VDD_1-VDD") (pintype "bidirectional"))
      (node (ref "L87") (pin "1-VDD") (pinfunction "VDD_1-VDD") (pintype "bidirectional"))
      (node (ref "L88") (pin "1-VDD") (pinfunction "VDD_1-VDD") (pintype "bidirectional"))
      (node (ref "L89") (pin "1-VDD") (pinfunction "VDD_1-VDD") (pintype "bidirectional"))
      (node (ref "L9") (pin "1-VDD") (pinfunction "VDD_1-VDD") (pintype "bidirectional"))
      (node (ref "L90") (pin "1-VDD") (pinfunction "VDD_1-VDD") (pintype "bidirectional"))
      (node (ref "L91") (pin "1-VDD") (pinfunction "VDD_1-VDD") (pintype "bidirectional"))
      (node (ref "L92") (pin "1-VDD") (pinfunction "VDD_1-VDD") (pintype "bidirectional"))
      (node (ref "L93") (pin "1-VDD") (pinfunction "VDD_1-VDD") (pintype "bidirectional"))
      (node (ref "L94") (pin "1-VDD") (pinfunction "VDD_1-VDD") (pintype "bidirectional"))
      (node (ref "L95") (pin "1-VDD") (pinfunction "VDD_1-VDD") (pintype "bidirectional"))
      (node (ref "L96") (pin "1-VDD") (pinfunction "VDD_1-VDD") (pintype "bidirectional"))
      (node (ref "L97") (pin "1-VDD") (pinfunction "VDD_1-VDD") (pintype "bidirectional"))
      (node (ref "L98") (pin "1-VDD") (pinfunction "VDD_1-VDD") (pintype "bidirectional"))
      (node (ref "L99") (pin "1-VDD") (pinfunction "VDD_1-VDD") (pintype "bidirectional"))
      (node (ref "Q3") (pin "3") (pinfunction "S_3") (pintype "passive"))
    )
    (net (code "160") (name "unconnected-(S2-S1-Pad2)") (class "Default")
      (node (ref "S2") (pin "2") (pinfunction "S1_2") (pintype "passive"))
    )
    (net (code "161") (name "unconnected-(S3-S1-Pad2)") (class "Default")
      (node (ref "S3") (pin "2") (pinfunction "S1_2") (pintype "passive"))
    )
    (net (code "162") (name "unconnected-(S4-S1-Pad2)") (class "Default")
      (node (ref "S4") (pin "2") (pinfunction "S1_2") (pintype "passive"))
    )
    (net (code "163") (name "unconnected-(S5-S1-Pad2)") (class "Default")
      (node (ref "S5") (pin "2") (pinfunction "S1_2") (pintype "passive"))
    )
    (net (code "164") (name "unconnected-(U$1-Pad2)") (class "Default")
      (node (ref "U$1") (pin "2") (pinfunction "2_2") (pintype "input"))
    )
    (net (code "165") (name "unconnected-(U$1-Pad3)") (class "Default")
      (node (ref "U$1") (pin "3") (pinfunction "3_3") (pintype "input"))
    )
    (net (code "166") (name "unconnected-(U$1-Pad4)") (class "Default")
      (node (ref "U$1") (pin "4") (pinfunction "4_4") (pintype "input"))
    )
  )
)
